# boatcc.net
KiCad netlist of a schematic drawn in EAGLE
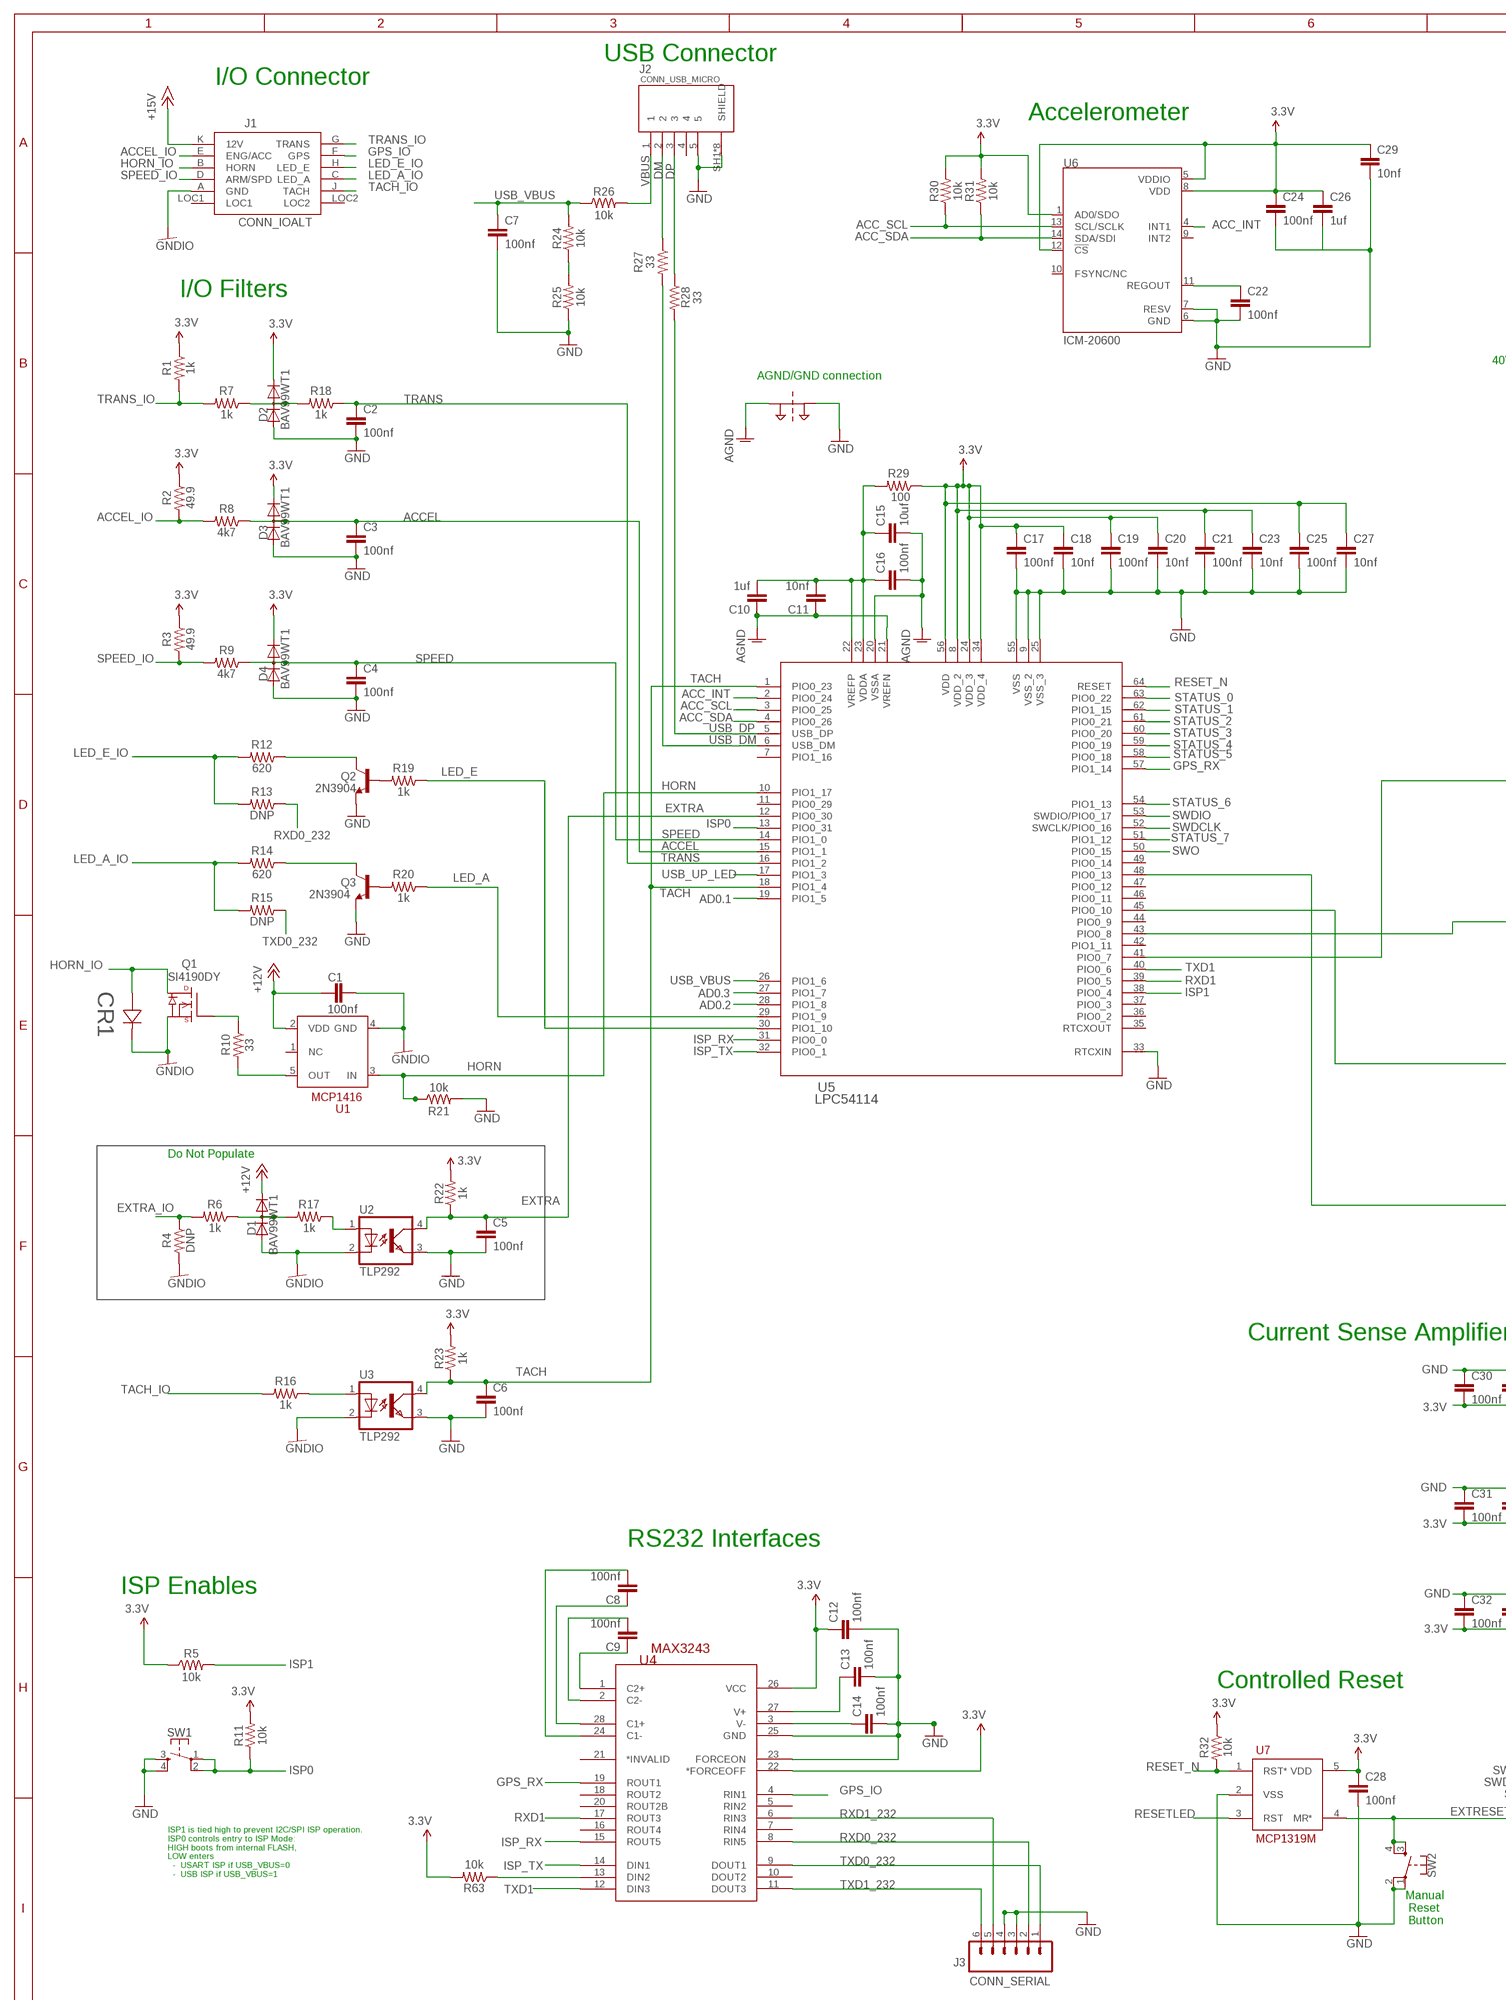
[diagram p0: schematic, sheet 1, part 1 of 2]
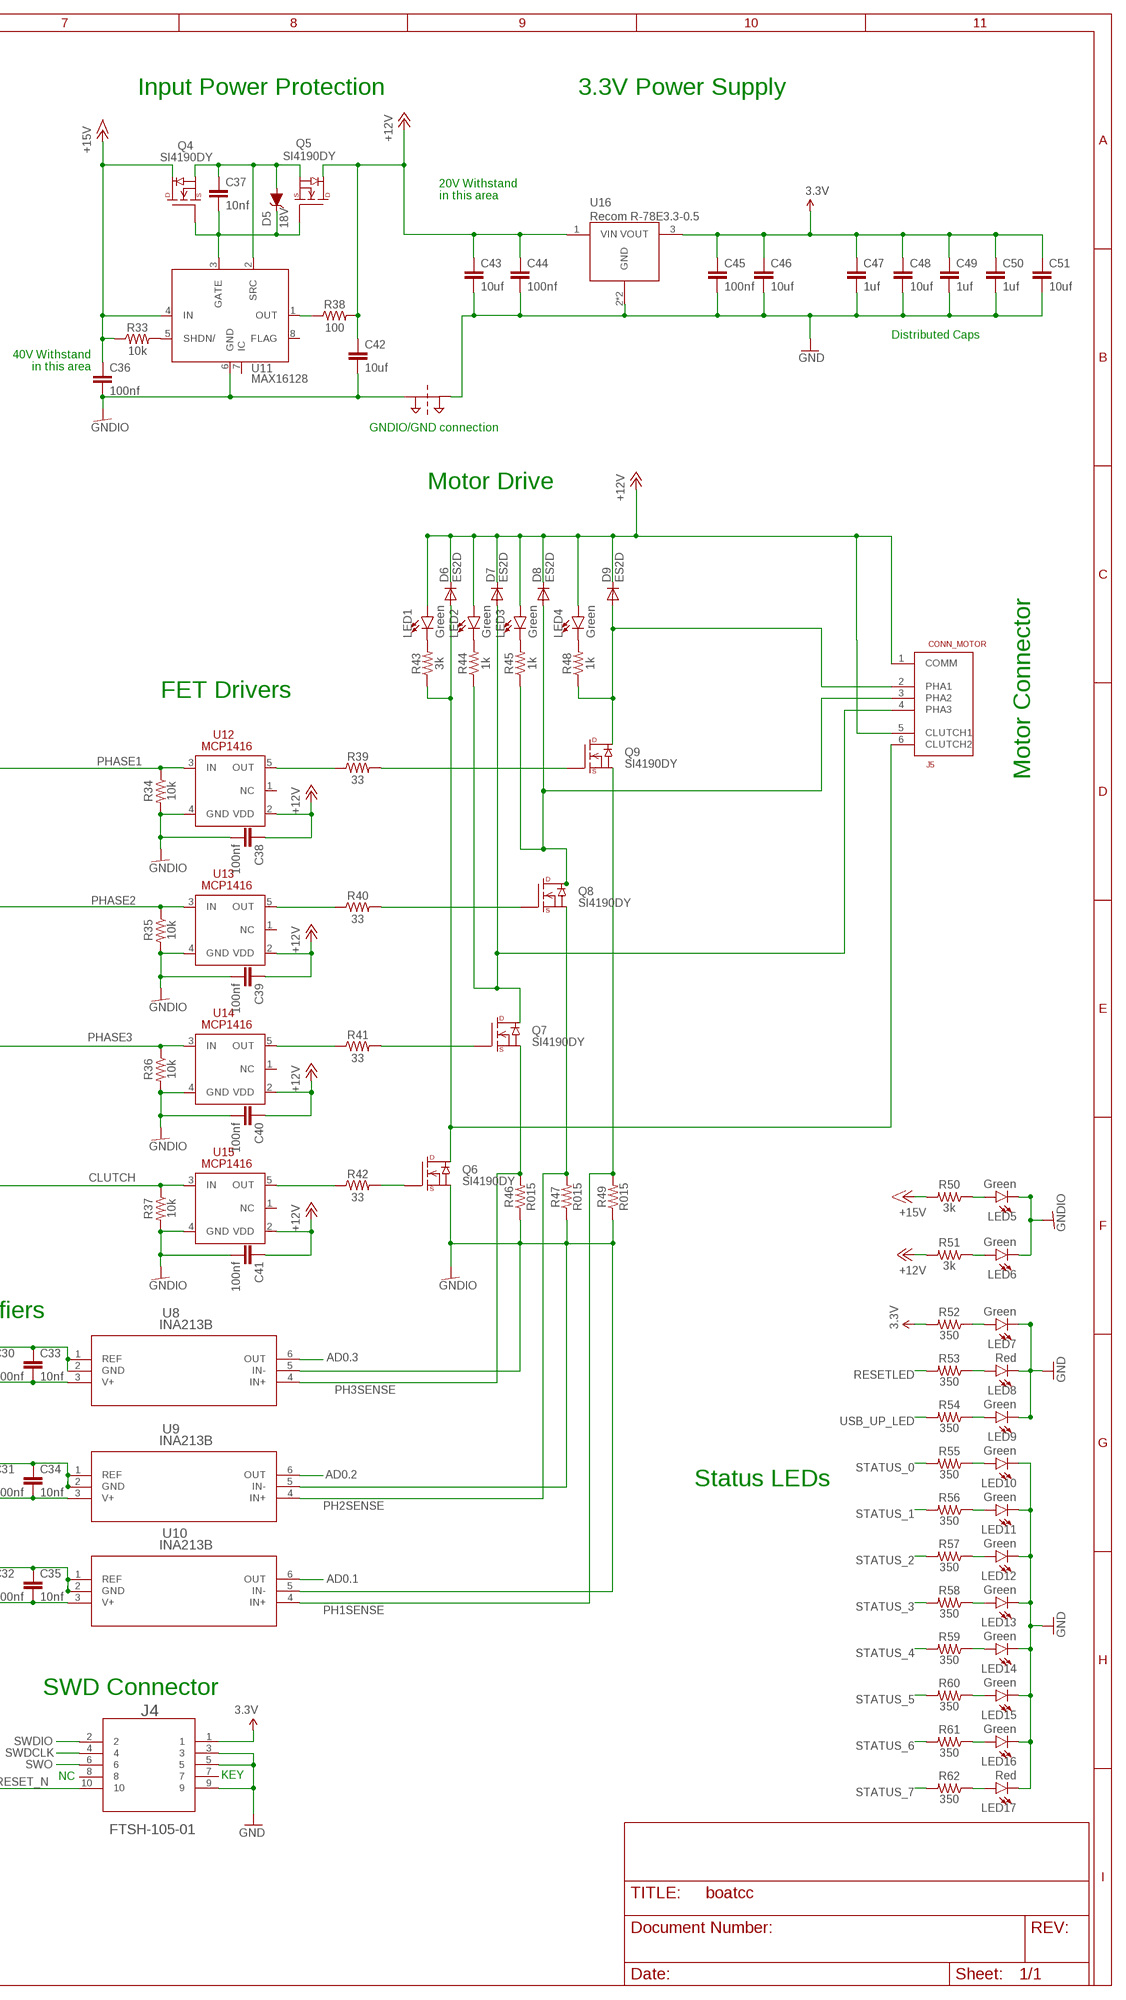
[diagram p1: schematic, sheet 1, part 2 of 2]

(export (version "E")
  (design (tool "Eeschema 10.0.6"))
  (components
    (comp (ref "C1")
      (value "100nf")
      (footprint "eagle-import:0805")
      (libsource (lib "eagle-import") (part "1CAP-0805"))
    )
    (comp (ref "C2")
      (value "100nf")
      (footprint "eagle-import:0805")
      (libsource (lib "eagle-import") (part "1CAP-0805"))
    )
    (comp (ref "C3")
      (value "100nf")
      (footprint "eagle-import:0805")
      (libsource (lib "eagle-import") (part "1CAP-0805"))
    )
    (comp (ref "C4")
      (value "100nf")
      (footprint "eagle-import:0805")
      (libsource (lib "eagle-import") (part "1CAP-0805"))
    )
    (comp (ref "C5")
      (value "100nf")
      (footprint "eagle-import:0805")
      (libsource (lib "eagle-import") (part "1CAP-0805"))
    )
    (comp (ref "C6")
      (value "100nf")
      (footprint "eagle-import:0805")
      (libsource (lib "eagle-import") (part "1CAP-0805"))
    )
    (comp (ref "C7")
      (value "100nf")
      (footprint "eagle-import:0805")
      (libsource (lib "eagle-import") (part "1CAP-0805"))
    )
    (comp (ref "C8")
      (value "100nf")
      (footprint "eagle-import:0805")
      (libsource (lib "eagle-import") (part "1CAP-0805"))
    )
    (comp (ref "C9")
      (value "100nf")
      (footprint "eagle-import:0805")
      (libsource (lib "eagle-import") (part "1CAP-0805"))
    )
    (comp (ref "C10")
      (value "1uf")
      (footprint "eagle-import:0805")
      (libsource (lib "eagle-import") (part "1CAP-0805"))
    )
    (comp (ref "C11")
      (value "10nf")
      (footprint "eagle-import:0805")
      (libsource (lib "eagle-import") (part "1CAP-0805"))
    )
    (comp (ref "C12")
      (value "100nf")
      (footprint "eagle-import:0805")
      (libsource (lib "eagle-import") (part "1CAP-0805"))
    )
    (comp (ref "C13")
      (value "100nf")
      (footprint "eagle-import:0805")
      (libsource (lib "eagle-import") (part "1CAP-0805"))
    )
    (comp (ref "C14")
      (value "100nf")
      (footprint "eagle-import:0805")
      (libsource (lib "eagle-import") (part "1CAP-0805"))
    )
    (comp (ref "C15")
      (value "10uf")
      (footprint "eagle-import:0805")
      (libsource (lib "eagle-import") (part "1CAP-0805"))
    )
    (comp (ref "C16")
      (value "100nf")
      (footprint "eagle-import:0805")
      (libsource (lib "eagle-import") (part "1CAP-0805"))
    )
    (comp (ref "C17")
      (value "100nf")
      (footprint "eagle-import:0805")
      (libsource (lib "eagle-import") (part "1CAP-0805"))
    )
    (comp (ref "C18")
      (value "10nf")
      (footprint "eagle-import:0805")
      (libsource (lib "eagle-import") (part "1CAP-0805"))
    )
    (comp (ref "C19")
      (value "100nf")
      (footprint "eagle-import:0805")
      (libsource (lib "eagle-import") (part "1CAP-0805"))
    )
    (comp (ref "C20")
      (value "10nf")
      (footprint "eagle-import:0805")
      (libsource (lib "eagle-import") (part "1CAP-0805"))
    )
    (comp (ref "C21")
      (value "100nf")
      (footprint "eagle-import:0805")
      (libsource (lib "eagle-import") (part "1CAP-0805"))
    )
    (comp (ref "C22")
      (value "100nf")
      (footprint "eagle-import:0805")
      (libsource (lib "eagle-import") (part "1CAP-0805"))
    )
    (comp (ref "C23")
      (value "10nf")
      (footprint "eagle-import:0805")
      (libsource (lib "eagle-import") (part "1CAP-0805"))
    )
    (comp (ref "C24")
      (value "100nf")
      (footprint "eagle-import:0805")
      (libsource (lib "eagle-import") (part "1CAP-0805"))
    )
    (comp (ref "C25")
      (value "100nf")
      (footprint "eagle-import:0805")
      (libsource (lib "eagle-import") (part "1CAP-0805"))
    )
    (comp (ref "C26")
      (value "1uf")
      (footprint "eagle-import:0805")
      (libsource (lib "eagle-import") (part "1CAP-0805"))
    )
    (comp (ref "C27")
      (value "10nf")
      (footprint "eagle-import:0805")
      (libsource (lib "eagle-import") (part "1CAP-0805"))
    )
    (comp (ref "C28")
      (value "100nf")
      (footprint "eagle-import:0805")
      (libsource (lib "eagle-import") (part "1CAP-0805"))
    )
    (comp (ref "C29")
      (value "10nf")
      (footprint "eagle-import:0805")
      (libsource (lib "eagle-import") (part "1CAP-0805"))
    )
    (comp (ref "C30")
      (value "100nf")
      (footprint "eagle-import:0805")
      (libsource (lib "eagle-import") (part "1CAP-0805"))
    )
    (comp (ref "C31")
      (value "100nf")
      (footprint "eagle-import:0805")
      (libsource (lib "eagle-import") (part "1CAP-0805"))
    )
    (comp (ref "C32")
      (value "100nf")
      (footprint "eagle-import:0805")
      (libsource (lib "eagle-import") (part "1CAP-0805"))
    )
    (comp (ref "C33")
      (value "10nf")
      (footprint "eagle-import:0805")
      (libsource (lib "eagle-import") (part "1CAP-0805"))
    )
    (comp (ref "C34")
      (value "10nf")
      (footprint "eagle-import:0805")
      (libsource (lib "eagle-import") (part "1CAP-0805"))
    )
    (comp (ref "C35")
      (value "10nf")
      (footprint "eagle-import:0805")
      (libsource (lib "eagle-import") (part "1CAP-0805"))
    )
    (comp (ref "C36")
      (value "100nf")
      (footprint "eagle-import:0805")
      (libsource (lib "eagle-import") (part "1CAP-0805"))
    )
    (comp (ref "C37")
      (value "10nf")
      (footprint "eagle-import:0805")
      (libsource (lib "eagle-import") (part "1CAP-0805"))
    )
    (comp (ref "C38")
      (value "100nf")
      (footprint "eagle-import:0805")
      (libsource (lib "eagle-import") (part "1CAP-0805"))
    )
    (comp (ref "C39")
      (value "100nf")
      (footprint "eagle-import:0805")
      (libsource (lib "eagle-import") (part "1CAP-0805"))
    )
    (comp (ref "C40")
      (value "100nf")
      (footprint "eagle-import:0805")
      (libsource (lib "eagle-import") (part "1CAP-0805"))
    )
    (comp (ref "C41")
      (value "100nf")
      (footprint "eagle-import:0805")
      (libsource (lib "eagle-import") (part "1CAP-0805"))
    )
    (comp (ref "C42")
      (value "10uf")
      (footprint "eagle-import:0805")
      (libsource (lib "eagle-import") (part "1CAP-0805"))
    )
    (comp (ref "C43")
      (value "10uf")
      (footprint "eagle-import:0805")
      (libsource (lib "eagle-import") (part "1CAP-0805"))
    )
    (comp (ref "C44")
      (value "100nf")
      (footprint "eagle-import:0805")
      (libsource (lib "eagle-import") (part "1CAP-0805"))
    )
    (comp (ref "C45")
      (value "100nf")
      (footprint "eagle-import:0805")
      (libsource (lib "eagle-import") (part "1CAP-0805"))
    )
    (comp (ref "C46")
      (value "10uf")
      (footprint "eagle-import:0805")
      (libsource (lib "eagle-import") (part "1CAP-0805"))
    )
    (comp (ref "C47")
      (value "1uf")
      (footprint "eagle-import:0805")
      (libsource (lib "eagle-import") (part "1CAP-0805"))
    )
    (comp (ref "C48")
      (value "10uf")
      (footprint "eagle-import:0805")
      (libsource (lib "eagle-import") (part "1CAP-0805"))
    )
    (comp (ref "C49")
      (value "1uf")
      (footprint "eagle-import:0805")
      (libsource (lib "eagle-import") (part "1CAP-0805"))
    )
    (comp (ref "C50")
      (value "1uf")
      (footprint "eagle-import:0805")
      (libsource (lib "eagle-import") (part "1CAP-0805"))
    )
    (comp (ref "C51")
      (value "10uf")
      (footprint "eagle-import:0805")
      (libsource (lib "eagle-import") (part "1CAP-0805"))
    )
    (comp (ref "CR1")
      (value "SMAJ45CASMASERIES-M")
      (footprint "eagle-import:SMASERIES-M")
      (fields
        (field (name "MANUFACTURER_PART_NUMBER") "SMAJ45CA")
        (field (name "DIGI-KEY_PART_NUMBER") "SMAJ24CALFCT-ND")
        (field (name "MANUFACTURER_PART_NUMBER_1") "SMAJ24CA")
      )
      (libsource (lib "eagle-import") (part "SMAJ45CASMASERIES-M"))
    )
    (comp (ref "D1")
      (value "BAV99WT1")
      (footprint "eagle-import:SC70")
      (fields
        (field (name "DIGI-KEY_PART_NUMBER") "BAV99WT1GOSCT-ND")
        (field (name "MF") "ON Semiconductor")
        (field (name "MP") "BAV99WT1G ")
      )
      (libsource (lib "eagle-import") (part "BAV99WT1"))
    )
    (comp (ref "D2")
      (value "BAV99WT1")
      (footprint "eagle-import:SC70")
      (fields
        (field (name "DIGI-KEY_PART_NUMBER") "BAV99WT1GOSCT-ND")
        (field (name "MF") "ON Semiconductor")
        (field (name "MP") "BAV99WT1G ")
      )
      (libsource (lib "eagle-import") (part "BAV99WT1"))
    )
    (comp (ref "D3")
      (value "BAV99WT1")
      (footprint "eagle-import:SC70")
      (fields
        (field (name "DIGI-KEY_PART_NUMBER") "BAV99WT1GOSCT-ND")
        (field (name "MF") "ON Semiconductor")
        (field (name "MP") "BAV99WT1G ")
      )
      (libsource (lib "eagle-import") (part "BAV99WT1"))
    )
    (comp (ref "D4")
      (value "BAV99WT1")
      (footprint "eagle-import:SC70")
      (fields
        (field (name "DIGI-KEY_PART_NUMBER") "BAV99WT1GOSCT-ND")
        (field (name "MF") "ON Semiconductor")
        (field (name "MP") "BAV99WT1G ")
      )
      (libsource (lib "eagle-import") (part "BAV99WT1"))
    )
    (comp (ref "D5")
      (value "18V")
      (footprint "eagle-import:SOD-323")
      (fields
        (field (name "DIGI-KEY_PART_NUMBER") "MM3Z18VT1GOSCT-ND ")
        (field (name "MF") "ON Semiconductor")
        (field (name "MP") "MM3Z18VT1G ")
      )
      (libsource (lib "eagle-import") (part "DIODE-ZENER-MM3Z3V3T1G"))
    )
    (comp (ref "D6")
      (value "ES2D")
      (footprint "eagle-import:SMB")
      (fields (field (name "DIGI-KEY_PART_NUMBER") "ES2DFSCT-ND") (field (name "MF") "ON Semiconductor"))
      (libsource (lib "eagle-import") (part "ES2D"))
    )
    (comp (ref "D7")
      (value "ES2D")
      (footprint "eagle-import:SMB")
      (fields (field (name "DIGI-KEY_PART_NUMBER") "ES2DFSCT-ND") (field (name "MF") "ON Semiconductor"))
      (libsource (lib "eagle-import") (part "ES2D"))
    )
    (comp (ref "D8")
      (value "ES2D")
      (footprint "eagle-import:SMB")
      (fields (field (name "DIGI-KEY_PART_NUMBER") "ES2DFSCT-ND") (field (name "MF") "ON Semiconductor"))
      (libsource (lib "eagle-import") (part "ES2D"))
    )
    (comp (ref "D9")
      (value "ES2D")
      (footprint "eagle-import:SMB")
      (fields (field (name "DIGI-KEY_PART_NUMBER") "ES2DFSCT-ND") (field (name "MF") "ON Semiconductor"))
      (libsource (lib "eagle-import") (part "ES2D"))
    )
    (comp (ref "J1")
      (value "CONN_IOALT")
      (footprint "eagle-import:CONN_IO")
      (libsource (lib "eagle-import") (part "CONN_IOALT"))
    )
    (comp (ref "J2")
      (value "CONN_USB_MICRO")
      (footprint "eagle-import:MOLEX_1050170001")
      (fields
        (field (name "DIGI-KEY_PART_NUMBER") "WM1399CT-ND")
        (field (name "MF") "Molex, LLC")
        (field (name "MP") "1050170001")
      )
      (libsource (lib "eagle-import") (part "USB_MICRO"))
    )
    (comp (ref "J3")
      (value "CONN_SERIAL")
      (footprint "eagle-import:1X06_LOCK")
      (libsource (lib "eagle-import") (part "CONN_06LOCK"))
    )
    (comp (ref "J4")
      (value "FTSH-105-01")
      (footprint "eagle-import:SAMTEC-FTSH-105-01-X-DV")
      (fields
        (field (name "DIGI-KEY_PART_NUMBER") "SAM13933CT-ND")
        (field (name "MF") "Samtec Inc.")
        (field (name "MP") "FTSH-105-01-L-DV-007-P-TR")
      )
      (libsource (lib "eagle-import") (part "SAMTEC-FTSH-105-01-X-DVJ"))
    )
    (comp (ref "J5")
      (value "CONN_MOTOR")
      (footprint "eagle-import:CONN_MOTOR")
      (libsource (lib "eagle-import") (part "CONN_MOTOR"))
    )
    (comp (ref "LED1")
      (value "Green")
      (footprint "eagle-import:LED_0805")
      (fields
        (field (name "DIGI-KEY_PART_NUMBER") "732-4986-1-ND ")
        (field (name "DIGI-KEY_PURCHASE_URL") "https://www.digikey.com/product-detail/en/wurth-electronics-inc/150080VS75000/732-4986-1-ND/4489922")
        (field (name "MF") "WURTH Electronics")
        (field (name "MP") "150080VS75000")
      )
      (libsource (lib "eagle-import") (part "1LED0805"))
    )
    (comp (ref "LED2")
      (value "Green")
      (footprint "eagle-import:LED_0805")
      (fields
        (field (name "DIGI-KEY_PART_NUMBER") "732-4986-1-ND ")
        (field (name "DIGI-KEY_PURCHASE_URL") "https://www.digikey.com/product-detail/en/wurth-electronics-inc/150080VS75000/732-4986-1-ND/4489922")
        (field (name "MF") "WURTH Electronics")
        (field (name "MP") "150080VS75000")
      )
      (libsource (lib "eagle-import") (part "1LED0805"))
    )
    (comp (ref "LED3")
      (value "Green")
      (footprint "eagle-import:LED_0805")
      (fields
        (field (name "DIGI-KEY_PART_NUMBER") "732-4986-1-ND ")
        (field (name "DIGI-KEY_PURCHASE_URL") "https://www.digikey.com/product-detail/en/wurth-electronics-inc/150080VS75000/732-4986-1-ND/4489922")
        (field (name "MF") "WURTH Electronics")
        (field (name "MP") "150080VS75000")
      )
      (libsource (lib "eagle-import") (part "1LED0805"))
    )
    (comp (ref "LED4")
      (value "Green")
      (footprint "eagle-import:LED_0805")
      (fields
        (field (name "DIGI-KEY_PART_NUMBER") "732-4986-1-ND ")
        (field (name "DIGI-KEY_PURCHASE_URL") "https://www.digikey.com/product-detail/en/wurth-electronics-inc/150080VS75000/732-4986-1-ND/4489922")
        (field (name "MF") "WURTH Electronics")
        (field (name "MP") "150080VS75000")
      )
      (libsource (lib "eagle-import") (part "1LED0805"))
    )
    (comp (ref "LED5")
      (value "Green")
      (footprint "eagle-import:LED_0805")
      (fields
        (field (name "DIGI-KEY_PART_NUMBER") "732-4986-1-ND ")
        (field (name "DIGI-KEY_PURCHASE_URL") "https://www.digikey.com/product-detail/en/wurth-electronics-inc/150080VS75000/732-4986-1-ND/4489922")
        (field (name "MF") "WURTH Electronics")
        (field (name "MP") "150080VS75000")
      )
      (libsource (lib "eagle-import") (part "1LED0805"))
    )
    (comp (ref "LED6")
      (value "Green")
      (footprint "eagle-import:LED_0805")
      (fields
        (field (name "DIGI-KEY_PART_NUMBER") "732-4986-1-ND ")
        (field (name "DIGI-KEY_PURCHASE_URL") "https://www.digikey.com/product-detail/en/wurth-electronics-inc/150080VS75000/732-4986-1-ND/4489922")
        (field (name "MF") "WURTH Electronics")
        (field (name "MP") "150080VS75000")
      )
      (libsource (lib "eagle-import") (part "1LED0805"))
    )
    (comp (ref "LED7")
      (value "Green")
      (footprint "eagle-import:LED_0805")
      (fields
        (field (name "DIGI-KEY_PART_NUMBER") "732-4986-1-ND ")
        (field (name "DIGI-KEY_PURCHASE_URL") "https://www.digikey.com/product-detail/en/wurth-electronics-inc/150080VS75000/732-4986-1-ND/4489922")
        (field (name "MF") "WURTH Electronics")
        (field (name "MP") "150080VS75000")
      )
      (libsource (lib "eagle-import") (part "1LED0805"))
    )
    (comp (ref "LED8")
      (value "Red")
      (footprint "eagle-import:LED_0805")
      (fields
        (field (name "DIGI-KEY_PART_NUMBER") "732-4984-1-ND ")
        (field (name "DIGI-KEY_PURCHASE_URL") "https://www.digikey.com/product-detail/en/wurth-electronics-inc/150080RS75000/732-4984-1-ND/4489916")
        (field (name "MF") "WURTH Electronics")
        (field (name "MP") "150080RS75000 ")
      )
      (libsource (lib "eagle-import") (part "1LED0805"))
    )
    (comp (ref "LED9")
      (value "Green")
      (footprint "eagle-import:LED_0805")
      (fields
        (field (name "DIGI-KEY_PART_NUMBER") "732-4986-1-ND ")
        (field (name "MF") "WURTH Electronics")
        (field (name "MP") "150080VS75000")
      )
      (libsource (lib "eagle-import") (part "1LED0805"))
    )
    (comp (ref "LED10")
      (value "Green")
      (footprint "eagle-import:LED_0805")
      (fields
        (field (name "DIGI-KEY_PART_NUMBER") "732-4986-1-ND ")
        (field (name "DIGI-KEY_PURCHASE_URL") "https://www.digikey.com/product-detail/en/wurth-electronics-inc/150080VS75000/732-4986-1-ND/4489922")
        (field (name "MF") "WURTH Electronics")
        (field (name "MP") "150080VS75000")
      )
      (libsource (lib "eagle-import") (part "1LED0805"))
    )
    (comp (ref "LED11")
      (value "Green")
      (footprint "eagle-import:LED_0805")
      (fields
        (field (name "DIGI-KEY_PART_NUMBER") "732-4986-1-ND ")
        (field (name "DIGI-KEY_PURCHASE_URL") "https://www.digikey.com/product-detail/en/wurth-electronics-inc/150080VS75000/732-4986-1-ND/4489922")
        (field (name "MF") "WURTH Electronics")
        (field (name "MP") "150080VS75000")
      )
      (libsource (lib "eagle-import") (part "1LED0805"))
    )
    (comp (ref "LED12")
      (value "Green")
      (footprint "eagle-import:LED_0805")
      (fields
        (field (name "DIGI-KEY_PART_NUMBER") "732-4986-1-ND ")
        (field (name "DIGI-KEY_PURCHASE_URL") "https://www.digikey.com/product-detail/en/wurth-electronics-inc/150080VS75000/732-4986-1-ND/4489922")
        (field (name "MF") "WURTH Electronics")
        (field (name "MP") "150080VS75000")
      )
      (libsource (lib "eagle-import") (part "1LED0805"))
    )
    (comp (ref "LED13")
      (value "Green")
      (footprint "eagle-import:LED_0805")
      (fields
        (field (name "DIGI-KEY_PART_NUMBER") "732-4986-1-ND ")
        (field (name "DIGI-KEY_PURCHASE_URL") "https://www.digikey.com/product-detail/en/wurth-electronics-inc/150080VS75000/732-4986-1-ND/4489922")
        (field (name "MF") "WURTH Electronics")
        (field (name "MP") "150080VS75000")
      )
      (libsource (lib "eagle-import") (part "1LED0805"))
    )
    (comp (ref "LED14")
      (value "Green")
      (footprint "eagle-import:LED_0805")
      (fields
        (field (name "DIGI-KEY_PART_NUMBER") "732-4986-1-ND ")
        (field (name "DIGI-KEY_PURCHASE_URL") "https://www.digikey.com/product-detail/en/wurth-electronics-inc/150080VS75000/732-4986-1-ND/4489922")
        (field (name "MF") "WURTH Electronics")
        (field (name "MP") "150080VS75000")
      )
      (libsource (lib "eagle-import") (part "1LED0805"))
    )
    (comp (ref "LED15")
      (value "Green")
      (footprint "eagle-import:LED_0805")
      (fields
        (field (name "DIGI-KEY_PART_NUMBER") "732-4986-1-ND ")
        (field (name "DIGI-KEY_PURCHASE_URL") "https://www.digikey.com/product-detail/en/wurth-electronics-inc/150080VS75000/732-4986-1-ND/4489922")
        (field (name "MF") "WURTH Electronics")
        (field (name "MP") "150080VS75000")
      )
      (libsource (lib "eagle-import") (part "1LED0805"))
    )
    (comp (ref "LED16")
      (value "Green")
      (footprint "eagle-import:LED_0805")
      (fields
        (field (name "DIGI-KEY_PART_NUMBER") "732-4986-1-ND ")
        (field (name "DIGI-KEY_PURCHASE_URL") "https://www.digikey.com/product-detail/en/wurth-electronics-inc/150080VS75000/732-4986-1-ND/4489922")
        (field (name "MF") "WURTH Electronics")
        (field (name "MP") "150080VS75000")
      )
      (libsource (lib "eagle-import") (part "1LED0805"))
    )
    (comp (ref "LED17")
      (value "Red")
      (footprint "eagle-import:LED_0805")
      (fields
        (field (name "DIGI-KEY_PART_NUMBER") "732-4984-1-ND ")
        (field (name "DIGI-KEY_PURCHASE_URL") "https://www.digikey.com/product-detail/en/wurth-electronics-inc/150080RS75000/732-4984-1-ND/4489916")
        (field (name "MF") "WURTH Electronics")
        (field (name "MP") "150080RS75000 ")
      )
      (libsource (lib "eagle-import") (part "1LED0805"))
    )
    (comp (ref "Q1")
      (value "SI4190DY")
      (footprint "eagle-import:SO-8")
      (fields (field (name "DIGI-KEY_PART_NUMBER") "SI4190ADY-T1-GE3") (field (name "MF") "Vishay Siliconix"))
      (libsource (lib "eagle-import") (part "SI4190DY"))
    )
    (comp (ref "Q2")
      (value "2N3904")
      (footprint "eagle-import:SOT23-3")
      (fields
        (field (name "DIGI-KEY_PART_NUMBER") "MMBT2222AWT1GOSCT-ND")
        (field (name "MF") "ON Semiconductor")
        (field (name "MP") "MMBT2222AWT1G")
      )
      (libsource (lib "eagle-import") (part "TRANS_NPN-MMBT2222AL"))
    )
    (comp (ref "Q3")
      (value "2N3904")
      (footprint "eagle-import:SOT23-3")
      (fields
        (field (name "DIGI-KEY_PART_NUMBER") "MMBT2222AWT1GOSCT-ND")
        (field (name "MF") "ON Semiconductor")
        (field (name "MP") "MMBT2222AWT1G")
      )
      (libsource (lib "eagle-import") (part "TRANS_NPN-MMBT2222AL"))
    )
    (comp (ref "Q4")
      (value "SI4190DY")
      (footprint "eagle-import:SO-8")
      (fields (field (name "DIGI-KEY_PART_NUMBER") "SI4190ADY-T1-GE3") (field (name "MF") "Vishay Siliconix"))
      (libsource (lib "eagle-import") (part "SI4190DY"))
    )
    (comp (ref "Q5")
      (value "SI4190DY")
      (footprint "eagle-import:SO-8")
      (fields (field (name "DIGI-KEY_PART_NUMBER") "SI4190ADY-T1-GE3") (field (name "MF") "Vishay Siliconix"))
      (libsource (lib "eagle-import") (part "SI4190DY"))
    )
    (comp (ref "Q6")
      (value "SI4190DY")
      (footprint "eagle-import:SO-8")
      (fields (field (name "DIGI-KEY_PART_NUMBER") "SI4190ADY-T1-GE3") (field (name "MF") "Vishay Siliconix"))
      (libsource (lib "eagle-import") (part "SI4190DY"))
    )
    (comp (ref "Q7")
      (value "SI4190DY")
      (footprint "eagle-import:SO-8")
      (fields (field (name "DIGI-KEY_PART_NUMBER") "SI4190ADY-T1-GE3") (field (name "MF") "Vishay Siliconix"))
      (libsource (lib "eagle-import") (part "SI4190DY"))
    )
    (comp (ref "Q8")
      (value "SI4190DY")
      (footprint "eagle-import:SO-8")
      (fields (field (name "DIGI-KEY_PART_NUMBER") "SI4190ADY-T1-GE3") (field (name "MF") "Vishay Siliconix"))
      (libsource (lib "eagle-import") (part "SI4190DY"))
    )
    (comp (ref "Q9")
      (value "SI4190DY")
      (footprint "eagle-import:SO-8")
      (fields (field (name "DIGI-KEY_PART_NUMBER") "SI4190ADY-T1-GE3") (field (name "MF") "Vishay Siliconix"))
      (libsource (lib "eagle-import") (part "SI4190DY"))
    )
    (comp (ref "R1")
      (value "1k")
      (footprint "eagle-import:0805")
      (libsource (lib "eagle-import") (part "1RES-0805"))
    )
    (comp (ref "R2")
      (value "49.9")
      (footprint "eagle-import:0805")
      (libsource (lib "eagle-import") (part "1RES-0805"))
    )
    (comp (ref "R3")
      (value "49.9")
      (footprint "eagle-import:0805")
      (libsource (lib "eagle-import") (part "1RES-0805"))
    )
    (comp (ref "R4")
      (value "DNP")
      (footprint "eagle-import:0805")
      (libsource (lib "eagle-import") (part "1RES-0805"))
    )
    (comp (ref "R5")
      (value "10k")
      (footprint "eagle-import:0805")
      (libsource (lib "eagle-import") (part "1RES-0805"))
    )
    (comp (ref "R6")
      (value "1k")
      (footprint "eagle-import:0805")
      (libsource (lib "eagle-import") (part "1RES-0805"))
    )
    (comp (ref "R7")
      (value "1k")
      (footprint "eagle-import:0805")
      (libsource (lib "eagle-import") (part "1RES-0805"))
    )
    (comp (ref "R8")
      (value "4k7")
      (footprint "eagle-import:0805")
      (libsource (lib "eagle-import") (part "1RES-0805"))
    )
    (comp (ref "R9")
      (value "4k7")
      (footprint "eagle-import:0805")
      (libsource (lib "eagle-import") (part "1RES-0805"))
    )
    (comp (ref "R10")
      (value "33")
      (footprint "eagle-import:0805")
      (libsource (lib "eagle-import") (part "1RES-0805"))
    )
    (comp (ref "R11")
      (value "10k")
      (footprint "eagle-import:0805")
      (libsource (lib "eagle-import") (part "1RES-0805"))
    )
    (comp (ref "R12")
      (value "620")
      (footprint "eagle-import:0805")
      (libsource (lib "eagle-import") (part "1RES-0805"))
    )
    (comp (ref "R13")
      (value "DNP")
      (footprint "eagle-import:0805")
      (libsource (lib "eagle-import") (part "1RES-0805"))
    )
    (comp (ref "R14")
      (value "620")
      (footprint "eagle-import:0805")
      (libsource (lib "eagle-import") (part "1RES-0805"))
    )
    (comp (ref "R15")
      (value "DNP")
      (footprint "eagle-import:0805")
      (libsource (lib "eagle-import") (part "1RES-0805"))
    )
    (comp (ref "R16")
      (value "1k")
      (footprint "eagle-import:0805")
      (libsource (lib "eagle-import") (part "1RES-0805"))
    )
    (comp (ref "R17")
      (value "1k")
      (footprint "eagle-import:0805")
      (libsource (lib "eagle-import") (part "1RES-0805"))
    )
    (comp (ref "R18")
      (value "1k")
      (footprint "eagle-import:0805")
      (libsource (lib "eagle-import") (part "1RES-0805"))
    )
    (comp (ref "R19")
      (value "1k")
      (footprint "eagle-import:0805")
      (libsource (lib "eagle-import") (part "1RES-0805"))
    )
    (comp (ref "R20")
      (value "1k")
      (footprint "eagle-import:0805")
      (libsource (lib "eagle-import") (part "1RES-0805"))
    )
    (comp (ref "R21")
      (value "10k")
      (footprint "eagle-import:0805")
      (libsource (lib "eagle-import") (part "1RES-0805"))
    )
    (comp (ref "R22")
      (value "1k")
      (footprint "eagle-import:0805")
      (libsource (lib "eagle-import") (part "1RES-0805"))
    )
    (comp (ref "R23")
      (value "1k")
      (footprint "eagle-import:0805")
      (libsource (lib "eagle-import") (part "1RES-0805"))
    )
    (comp (ref "R24")
      (value "10k")
      (footprint "eagle-import:0805")
      (libsource (lib "eagle-import") (part "1RES-0805"))
    )
    (comp (ref "R25")
      (value "10k")
      (footprint "eagle-import:0805")
      (libsource (lib "eagle-import") (part "1RES-0805"))
    )
    (comp (ref "R26")
      (value "10k")
      (footprint "eagle-import:0805")
      (libsource (lib "eagle-import") (part "1RES-0805"))
    )
    (comp (ref "R27")
      (value "33")
      (footprint "eagle-import:0805")
      (libsource (lib "eagle-import") (part "1RES-0805"))
    )
    (comp (ref "R28")
      (value "33")
      (footprint "eagle-import:0805")
      (libsource (lib "eagle-import") (part "1RES-0805"))
    )
    (comp (ref "R29")
      (value "100")
      (footprint "eagle-import:0805")
      (libsource (lib "eagle-import") (part "1RES-0805"))
    )
    (comp (ref "R30")
      (value "10k")
      (footprint "eagle-import:0805")
      (libsource (lib "eagle-import") (part "1RES-0805"))
    )
    (comp (ref "R31")
      (value "10k")
      (footprint "eagle-import:0805")
      (libsource (lib "eagle-import") (part "1RES-0805"))
    )
    (comp (ref "R32")
      (value "10k")
      (footprint "eagle-import:0805")
      (libsource (lib "eagle-import") (part "1RES-0805"))
    )
    (comp (ref "R33")
      (value "10k")
      (footprint "eagle-import:0805")
      (libsource (lib "eagle-import") (part "1RES-0805"))
    )
    (comp (ref "R34")
      (value "10k")
      (footprint "eagle-import:0805")
      (libsource (lib "eagle-import") (part "1RES-0805"))
    )
    (comp (ref "R35")
      (value "10k")
      (footprint "eagle-import:0805")
      (libsource (lib "eagle-import") (part "1RES-0805"))
    )
    (comp (ref "R36")
      (value "10k")
      (footprint "eagle-import:0805")
      (libsource (lib "eagle-import") (part "1RES-0805"))
    )
    (comp (ref "R37")
      (value "10k")
      (footprint "eagle-import:0805")
      (libsource (lib "eagle-import") (part "1RES-0805"))
    )
    (comp (ref "R38")
      (value "100")
      (footprint "eagle-import:0805")
      (libsource (lib "eagle-import") (part "1RES-0805"))
    )
    (comp (ref "R39")
      (value "33")
      (footprint "eagle-import:0805")
      (libsource (lib "eagle-import") (part "1RES-0805"))
    )
    (comp (ref "R40")
      (value "33")
      (footprint "eagle-import:0805")
      (libsource (lib "eagle-import") (part "1RES-0805"))
    )
    (comp (ref "R41")
      (value "33")
      (footprint "eagle-import:0805")
      (libsource (lib "eagle-import") (part "1RES-0805"))
    )
    (comp (ref "R42")
      (value "33")
      (footprint "eagle-import:0805")
      (libsource (lib "eagle-import") (part "1RES-0805"))
    )
    (comp (ref "R43")
      (value "3k")
      (footprint "eagle-import:0805")
      (libsource (lib "eagle-import") (part "1RES-0805"))
    )
    (comp (ref "R44")
      (value "1k")
      (footprint "eagle-import:0805")
      (libsource (lib "eagle-import") (part "1RES-0805"))
    )
    (comp (ref "R45")
      (value "1k")
      (footprint "eagle-import:0805")
      (libsource (lib "eagle-import") (part "1RES-0805"))
    )
    (comp (ref "R46")
      (value "R015")
      (footprint "eagle-import:1206")
      (fields (field (name "DIGI-KEY_PART_NUMBER") "408-1572-1-ND"))
      (libsource (lib "eagle-import") (part "1RES-1206"))
    )
    (comp (ref "R47")
      (value "R015")
      (footprint "eagle-import:1206")
      (fields (field (name "DIGI-KEY_PART_NUMBER") "408-1572-1-ND"))
      (libsource (lib "eagle-import") (part "1RES-1206"))
    )
    (comp (ref "R48")
      (value "1k")
      (footprint "eagle-import:0805")
      (libsource (lib "eagle-import") (part "1RES-0805"))
    )
    (comp (ref "R49")
      (value "R015")
      (footprint "eagle-import:1206")
      (fields (field (name "DIGI-KEY_PART_NUMBER") "408-1572-1-ND"))
      (libsource (lib "eagle-import") (part "1RES-1206"))
    )
    (comp (ref "R50")
      (value "3k")
      (footprint "eagle-import:0805")
      (libsource (lib "eagle-import") (part "1RES-0805"))
    )
    (comp (ref "R51")
      (value "3k")
      (footprint "eagle-import:0805")
      (libsource (lib "eagle-import") (part "1RES-0805"))
    )
    (comp (ref "R52")
      (value "350")
      (footprint "eagle-import:0805")
      (libsource (lib "eagle-import") (part "1RES-0805"))
    )
    (comp (ref "R53")
      (value "350")
      (footprint "eagle-import:0805")
      (libsource (lib "eagle-import") (part "1RES-0805"))
    )
    (comp (ref "R54")
      (value "350")
      (footprint "eagle-import:0805")
      (libsource (lib "eagle-import") (part "1RES-0805"))
    )
    (comp (ref "R55")
      (value "350")
      (footprint "eagle-import:0805")
      (libsource (lib "eagle-import") (part "1RES-0805"))
    )
    (comp (ref "R56")
      (value "350")
      (footprint "eagle-import:0805")
      (libsource (lib "eagle-import") (part "1RES-0805"))
    )
    (comp (ref "R57")
      (value "350")
      (footprint "eagle-import:0805")
      (libsource (lib "eagle-import") (part "1RES-0805"))
    )
    (comp (ref "R58")
      (value "350")
      (footprint "eagle-import:0805")
      (libsource (lib "eagle-import") (part "1RES-0805"))
    )
    (comp (ref "R59")
      (value "350")
      (footprint "eagle-import:0805")
      (libsource (lib "eagle-import") (part "1RES-0805"))
    )
    (comp (ref "R60")
      (value "350")
      (footprint "eagle-import:0805")
      (libsource (lib "eagle-import") (part "1RES-0805"))
    )
    (comp (ref "R61")
      (value "350")
      (footprint "eagle-import:0805")
      (libsource (lib "eagle-import") (part "1RES-0805"))
    )
    (comp (ref "R62")
      (value "350")
      (footprint "eagle-import:0805")
      (libsource (lib "eagle-import") (part "1RES-0805"))
    )
    (comp (ref "R63")
      (value "10k")
      (footprint "eagle-import:0805")
      (libsource (lib "eagle-import") (part "1RES-0805"))
    )
    (comp (ref "SUPPLY1")
      (value "2PT_GND_TIE")
      (footprint "eagle-import:2PT_GND_TIE")
      (libsource (lib "eagle-import") (part "2PT_GND_TIE"))
    )
    (comp (ref "SUPPLY2")
      (value "2PT_GND_TIE")
      (footprint "eagle-import:2PT_GND_TIE")
      (libsource (lib "eagle-import") (part "2PT_GND_TIE"))
    )
    (comp (ref "SW1")
      (value "MOMENTARY-SWITCH-SPST-2-SMD-5.2MM")
      (footprint "eagle-import:TACTILE_SWITCH_SMD_5.2MM")
      (fields
        (field (name "DIGI-KEY_PART_NUMBER") "CKN9104CT-ND")
        (field (name "MF") "C&K")
        (field (name "MP") "PTS525SM15SMTR2 LFS")
      )
      (libsource (lib "eagle-import") (part "MOMENTARY-SWITCH-SPST-2-SMD-5.2MM"))
    )
    (comp (ref "SW2")
      (value "MOMENTARY-SWITCH-SPST-2-SMD-5.2MM")
      (footprint "eagle-import:TACTILE_SWITCH_SMD_5.2MM")
      (fields
        (field (name "DIGI-KEY_PART_NUMBER") "CKN9104CT-ND")
        (field (name "MF") "C&K")
        (field (name "MP") "PTS525SM15SMTR2 LFS")
      )
      (libsource (lib "eagle-import") (part "MOMENTARY-SWITCH-SPST-2-SMD-5.2MM"))
    )
    (comp (ref "U1")
      (value "MCP1416")
      (footprint "eagle-import:SOT-23-5_MC-M")
      (fields
        (field (name "DIGI-KEY_PART_NUMBER") "MCP1416T-E/OTCT-ND")
        (field (name "MF") "Microchip Technology")
      )
      (libsource (lib "eagle-import") (part "MCP1416SOT-23-5_MCM"))
    )
    (comp (ref "U2")
      (value "TLP292")
      (footprint "eagle-import:MINI-FLAT-4")
      (fields
        (field (name "DIGI-KEY_PART_NUMBER") "TLP291(GB-TPSECT-ND ")
        (field (name "MF") "Toshiba Semiconductor")
        (field (name "MP") "TLP291(GB-TP,SE")
        (field (name "DIGI-KEY_PART_NUMBER_1") "TLP292(GB-TPLECT-ND ")
        (field (name "DIGI-KEY_PURCHASE_URL") "https://www.digikey.com/product-detail/en/toshiba-semiconductor-and-storage/TLP292-GB-TPLE/TLP292-GB-TPLECT-ND/4562959")
        (field (name "MP_1") "TLP292(GB-TPL,E")
      )
      (libsource (lib "eagle-import") (part "TLP290"))
    )
    (comp (ref "U3")
      (value "TLP292")
      (footprint "eagle-import:MINI-FLAT-4")
      (fields
        (field (name "DIGI-KEY_PART_NUMBER") "TLP291(GB-TPSECT-ND ")
        (field (name "MF") "Toshiba Semiconductor")
        (field (name "MP") "TLP291(GB-TP,SE")
        (field (name "DIGI-KEY_PART_NUMBER_1") "TLP292(GB-TPLECT-ND ")
        (field (name "DIGI-KEY_PURCHASE_URL") "https://www.digikey.com/product-detail/en/toshiba-semiconductor-and-storage/TLP292-GB-TPLE/TLP292-GB-TPLECT-ND/4562959")
        (field (name "MP_1") "TLP292(GB-TPL,E")
      )
      (libsource (lib "eagle-import") (part "TLP290"))
    )
    (comp (ref "U4")
      (value "MAX3243")
      (footprint "eagle-import:PW28-M")
      (fields
        (field (name "DIGI-KEY_PART_NUMBER") "296-19809-1-ND")
        (field (name "MF") "Texas Instruments")
        (field (name "MP") "MAX3243EIDWR")
      )
      (libsource (lib "eagle-import") (part "MAX3243_PW_28HEAVY"))
    )
    (comp (ref "U5")
      (value "LPC54114")
      (footprint "eagle-import:LQFP64_10X10-M")
      (fields
        (field (name "DIGI-KEY_PART_NUMBER") "568-13034-ND")
        (field (name "MF") "NXP")
        (field (name "MP") "LPC54114J256BD64QL")
      )
      (libsource (lib "eagle-import") (part "LPC5411XJXXXBD64LQFP64_10X10-M"))
    )
    (comp (ref "U6")
      (value "ICM-20600")
      (footprint "eagle-import:PQFN50P250X300X97-14N")
      (fields (field (name "DIGI-KEY_PART_NUMBER") "1428-1147-1-ND") (field (name "MF") "TDK InvenSense"))
      (libsource (lib "eagle-import") (part "ICM-20600"))
    )
    (comp (ref "U7")
      (value "MCP1319M")
      (footprint "eagle-import:SOT23-5")
      (fields
        (field (name "DIGI-KEY_PART_NUMBER") "MCP1319MT-29LE/OTCT-ND ")
        (field (name "MF") "Microchip Technology")
        (field (name "MP") "MCP1319MT-29LE/OT ")
      )
      (libsource (lib "eagle-import") (part "MCP1319M"))
    )
    (comp (ref "U8")
      (value "INA213B")
      (footprint "eagle-import:DCK6-M")
      (fields
        (field (name "MANUFACTURER_PART_NUMBER") "INA213AIDCKR")
        (field (name "DIGI-KEY_PART_NUMBER") "296-40129-1-ND")
        (field (name "MANUFACTURER_PART_NUMBER_1") "INA213BIDCKR")
      )
      (libsource (lib "eagle-import") (part "INA213AIDCKRDCK6-M"))
    )
    (comp (ref "U9")
      (value "INA213B")
      (footprint "eagle-import:DCK6-M")
      (fields
        (field (name "MANUFACTURER_PART_NUMBER") "INA213AIDCKR")
        (field (name "DIGI-KEY_PART_NUMBER") "296-40129-1-ND")
        (field (name "MANUFACTURER_PART_NUMBER_1") "INA213BIDCKR")
      )
      (libsource (lib "eagle-import") (part "INA213AIDCKRDCK6-M"))
    )
    (comp (ref "U10")
      (value "INA213B")
      (footprint "eagle-import:DCK6-M")
      (fields
        (field (name "MANUFACTURER_PART_NUMBER") "INA213AIDCKR")
        (field (name "DIGI-KEY_PART_NUMBER") "296-40129-1-ND")
        (field (name "MANUFACTURER_PART_NUMBER_1") "INA213BIDCKR")
      )
      (libsource (lib "eagle-import") (part "INA213AIDCKRDCK6-M"))
    )
    (comp (ref "U11")
      (value "MAX16128")
      (footprint "eagle-import:UMAX8")
      (fields
        (field (name "DIGI-KEY_PART_NUMBER") "MAX16129UADFD+-ND")
        (field (name "MF") "MAXIM")
        (field (name "MP") "MAX16129UADFD+")
      )
      (libsource (lib "eagle-import") (part "MAX16128"))
    )
    (comp (ref "U12")
      (value "MCP1416")
      (footprint "eagle-import:SOT-23-5_MC-M")
      (fields
        (field (name "DIGI-KEY_PART_NUMBER") "MCP1416T-E/OTCT-ND")
        (field (name "MF") "Microchip Technology")
      )
      (libsource (lib "eagle-import") (part "MCP1416SOT-23-5_MCM"))
    )
    (comp (ref "U13")
      (value "MCP1416")
      (footprint "eagle-import:SOT-23-5_MC-M")
      (fields
        (field (name "DIGI-KEY_PART_NUMBER") "MCP1416T-E/OTCT-ND")
        (field (name "MF") "Microchip Technology")
      )
      (libsource (lib "eagle-import") (part "MCP1416SOT-23-5_MCM"))
    )
    (comp (ref "U14")
      (value "MCP1416")
      (footprint "eagle-import:SOT-23-5_MC-M")
      (fields
        (field (name "DIGI-KEY_PART_NUMBER") "MCP1416T-E/OTCT-ND")
        (field (name "MF") "Microchip Technology")
      )
      (libsource (lib "eagle-import") (part "MCP1416SOT-23-5_MCM"))
    )
    (comp (ref "U15")
      (value "MCP1416")
      (footprint "eagle-import:SOT-23-5_MC-M")
      (fields
        (field (name "DIGI-KEY_PART_NUMBER") "MCP1416T-E/OTCT-ND")
        (field (name "MF") "Microchip Technology")
      )
      (libsource (lib "eagle-import") (part "MCP1416SOT-23-5_MCM"))
    )
    (comp (ref "U16")
      (value "Recom R-78E3.3-0.5")
      (footprint "eagle-import:D2PACK_A")
      (fields
        (field (name "ALT_DIGI-KEY_PART_NUMBER") "945-1661-5-ND")
        (field (name "DIGI-KEY_PART_NUMBER") "497-5225-1-ND ")
        (field (name "MF") "STMicroelectronics")
      )
      (libsource (lib "eagle-import") (part "LM2931_FIXEDD2PAK/TO263"))
    )
  )
  (nets
    (net (code "1") (name "+12V") (class "Default")
      (node (ref "C1") (pin "1") (pinfunction "1_1") (pintype "passive"))
      (node (ref "C38") (pin "1") (pinfunction "1_1") (pintype "passive"))
      (node (ref "C39") (pin "1") (pinfunction "1_1") (pintype "passive"))
      (node (ref "C40") (pin "1") (pinfunction "1_1") (pintype "passive"))
      (node (ref "C41") (pin "1") (pinfunction "1_1") (pintype "passive"))
      (node (ref "C42") (pin "1") (pinfunction "1_1") (pintype "passive"))
      (node (ref "C43") (pin "1") (pinfunction "1_1") (pintype "passive"))
      (node (ref "C44") (pin "1") (pinfunction "1_1") (pintype "passive"))
      (node (ref "D1") (pin "2") (pinfunction "C_2") (pintype "passive"))
      (node (ref "D6") (pin "C") (pinfunction "C_C") (pintype "passive"))
      (node (ref "D7") (pin "C") (pinfunction "C_C") (pintype "passive"))
      (node (ref "D8") (pin "C") (pinfunction "C_C") (pintype "passive"))
      (node (ref "D9") (pin "C") (pinfunction "C_C") (pintype "passive"))
      (node (ref "J5") (pin "1") (pinfunction "COMM_1") (pintype "bidirectional"))
      (node (ref "J5") (pin "5") (pinfunction "CLUTCH1_5") (pintype "bidirectional"))
      (node (ref "LED1") (pin "A") (pinfunction "A_A") (pintype "passive"))
      (node (ref "LED2") (pin "A") (pinfunction "A_A") (pintype "passive"))
      (node (ref "LED3") (pin "A") (pinfunction "A_A") (pintype "passive"))
      (node (ref "LED4") (pin "A") (pinfunction "A_A") (pintype "passive"))
      (node (ref "Q5") (pin "5") (pinfunction "D_5") (pintype "passive"))
      (node (ref "Q5") (pin "6") (pinfunction "D_6") (pintype "passive"))
      (node (ref "Q5") (pin "7") (pinfunction "D_7") (pintype "passive"))
      (node (ref "Q5") (pin "8") (pinfunction "D_8") (pintype "passive"))
      (node (ref "R38") (pin "2") (pinfunction "2_2") (pintype "passive"))
      (node (ref "R51") (pin "2") (pinfunction "2_2") (pintype "passive"))
      (node (ref "U1") (pin "2") (pinfunction "VDD_2") (pintype "passive"))
      (node (ref "U12") (pin "2") (pinfunction "VDD_2") (pintype "passive"))
      (node (ref "U13") (pin "2") (pinfunction "VDD_2") (pintype "passive"))
      (node (ref "U14") (pin "2") (pinfunction "VDD_2") (pintype "passive"))
      (node (ref "U15") (pin "2") (pinfunction "VDD_2") (pintype "passive"))
      (node (ref "U16") (pin "1") (pinfunction "VIN_1") (pintype "bidirectional"))
    )
    (net (code "2") (name "+15V") (class "Default")
      (node (ref "C36") (pin "1") (pinfunction "1_1") (pintype "passive"))
      (node (ref "J1") (pin "K") (pinfunction "12V_K") (pintype "bidirectional"))
      (node (ref "Q4") (pin "5") (pinfunction "D_5") (pintype "passive"))
      (node (ref "Q4") (pin "6") (pinfunction "D_6") (pintype "passive"))
      (node (ref "Q4") (pin "7") (pinfunction "D_7") (pintype "passive"))
      (node (ref "Q4") (pin "8") (pinfunction "D_8") (pintype "passive"))
      (node (ref "R33") (pin "1") (pinfunction "1_1") (pintype "passive"))
      (node (ref "R50") (pin "2") (pinfunction "2_2") (pintype "passive"))
      (node (ref "U11") (pin "4") (pinfunction "IN_4") (pintype "input"))
    )
    (net (code "3") (name "/ACCEL") (class "Default")
      (node (ref "C3") (pin "1") (pinfunction "1_1") (pintype "passive"))
      (node (ref "D3") (pin "3") (pinfunction "AC_3") (pintype "passive"))
      (node (ref "R8") (pin "1") (pinfunction "1_1") (pintype "passive"))
      (node (ref "U5") (pin "15") (pinfunction "PIO1_1_15") (pintype "bidirectional"))
    )
    (net (code "4") (name "/ACCEL_IO") (class "Default")
      (node (ref "J1") (pin "E") (pinfunction "ENG/ACC_E") (pintype "bidirectional"))
      (node (ref "R2") (pin "2") (pinfunction "2_2") (pintype "passive"))
      (node (ref "R8") (pin "2") (pinfunction "2_2") (pintype "passive"))
    )
    (net (code "5") (name "/ACC_INT") (class "Default")
      (node (ref "U5") (pin "2") (pinfunction "PIO0_24_2") (pintype "bidirectional"))
      (node (ref "U6") (pin "4") (pinfunction "INT1_4") (pintype "output"))
    )
    (net (code "6") (name "/ACC_SCL") (class "Default")
      (node (ref "R30") (pin "1") (pinfunction "1_1") (pintype "passive"))
      (node (ref "U5") (pin "3") (pinfunction "PIO0_25_3") (pintype "bidirectional"))
      (node (ref "U6") (pin "13") (pinfunction "SCL/SCLK_13") (pintype "bidirectional"))
    )
    (net (code "7") (name "/ACC_SDA") (class "Default")
      (node (ref "R31") (pin "1") (pinfunction "1_1") (pintype "passive"))
      (node (ref "U5") (pin "4") (pinfunction "PIO0_26_4") (pintype "bidirectional"))
      (node (ref "U6") (pin "14") (pinfunction "SDA/SDI_14") (pintype "bidirectional"))
    )
    (net (code "8") (name "/AD0.1") (class "Default")
      (node (ref "U10") (pin "6") (pinfunction "OUT_6") (pintype "output"))
      (node (ref "U5") (pin "19") (pinfunction "PIO1_5_19") (pintype "bidirectional"))
    )
    (net (code "9") (name "/AD0.2") (class "Default")
      (node (ref "U5") (pin "28") (pinfunction "PIO1_8_28") (pintype "bidirectional"))
      (node (ref "U9") (pin "6") (pinfunction "OUT_6") (pintype "output"))
    )
    (net (code "10") (name "/AD0.3") (class "Default")
      (node (ref "U5") (pin "27") (pinfunction "PIO1_7_27") (pintype "bidirectional"))
      (node (ref "U8") (pin "6") (pinfunction "OUT_6") (pintype "output"))
    )
    (net (code "11") (name "/CLUTCH") (class "Default")
      (node (ref "R37") (pin "1") (pinfunction "1_1") (pintype "passive"))
      (node (ref "U15") (pin "3") (pinfunction "IN_3") (pintype "passive"))
      (node (ref "U5") (pin "48") (pinfunction "PIO0_13_48") (pintype "bidirectional"))
    )
    (net (code "12") (name "/DM") (class "Default")
      (node (ref "J2") (pin "2") (pinfunction "2_2") (pintype "passive"))
      (node (ref "R27") (pin "1") (pinfunction "1_1") (pintype "passive"))
    )
    (net (code "13") (name "/DP") (class "Default")
      (node (ref "J2") (pin "3") (pinfunction "3_3") (pintype "passive"))
      (node (ref "R28") (pin "1") (pinfunction "1_1") (pintype "passive"))
    )
    (net (code "14") (name "/EXTRA") (class "Default")
      (node (ref "C5") (pin "1") (pinfunction "1_1") (pintype "passive"))
      (node (ref "R22") (pin "1") (pinfunction "1_1") (pintype "passive"))
      (node (ref "U2") (pin "4") (pinfunction "COL_4") (pintype "passive"))
      (node (ref "U5") (pin "12") (pinfunction "PIO0_30_12") (pintype "bidirectional"))
    )
    (net (code "15") (name "/EXTRA_IO") (class "Default")
      (node (ref "R4") (pin "1") (pinfunction "1_1") (pintype "passive"))
      (node (ref "R6") (pin "2") (pinfunction "2_2") (pintype "passive"))
    )
    (net (code "16") (name "/EXTRESET_N") (class "Default")
      (node (ref "J4") (pin "10") (pinfunction "10_10") (pintype "passive"))
      (node (ref "SW2") (pin "3") (pinfunction "3_3") (pintype "passive"))
      (node (ref "SW2") (pin "4") (pinfunction "4_4") (pintype "passive"))
      (node (ref "U7") (pin "4") (pinfunction "MR*_4") (pintype "bidirectional"))
    )
    (net (code "17") (name "/GPS_IO") (class "Default")
      (node (ref "J1") (pin "F") (pinfunction "GPS_F") (pintype "bidirectional"))
      (node (ref "U4") (pin "4") (pinfunction "RIN1_4") (pintype "passive"))
    )
    (net (code "18") (name "/GPS_RX") (class "Default")
      (node (ref "U4") (pin "19") (pinfunction "ROUT1_19") (pintype "passive"))
      (node (ref "U5") (pin "57") (pinfunction "PIO1_14_57") (pintype "bidirectional"))
    )
    (net (code "19") (name "/HORN") (class "Default")
      (node (ref "R21") (pin "1") (pinfunction "1_1") (pintype "passive"))
      (node (ref "U1") (pin "3") (pinfunction "IN_3") (pintype "passive"))
      (node (ref "U5") (pin "10") (pinfunction "PIO1_17_10") (pintype "bidirectional"))
    )
    (net (code "20") (name "/HORN_IO") (class "Default")
      (node (ref "CR1") (pin "2") (pinfunction "1_2") (pintype "passive"))
      (node (ref "J1") (pin "B") (pinfunction "HORN_B") (pintype "bidirectional"))
      (node (ref "Q1") (pin "5") (pinfunction "D_5") (pintype "passive"))
      (node (ref "Q1") (pin "6") (pinfunction "D_6") (pintype "passive"))
      (node (ref "Q1") (pin "7") (pinfunction "D_7") (pintype "passive"))
      (node (ref "Q1") (pin "8") (pinfunction "D_8") (pintype "passive"))
    )
    (net (code "21") (name "/ISP0") (class "Default")
      (node (ref "R11") (pin "1") (pinfunction "1_1") (pintype "passive"))
      (node (ref "SW1") (pin "1") (pinfunction "1_1") (pintype "passive"))
      (node (ref "SW1") (pin "2") (pinfunction "2_2") (pintype "passive"))
      (node (ref "U5") (pin "13") (pinfunction "PIO0_31_13") (pintype "bidirectional"))
    )
    (net (code "22") (name "/ISP1") (class "Default")
      (node (ref "R5") (pin "2") (pinfunction "2_2") (pintype "passive"))
      (node (ref "U5") (pin "38") (pinfunction "PIO0_4_38") (pintype "bidirectional"))
    )
    (net (code "23") (name "/ISP_RX") (class "Default")
      (node (ref "U4") (pin "15") (pinfunction "ROUT5_15") (pintype "passive"))
      (node (ref "U5") (pin "31") (pinfunction "PIO0_0_31") (pintype "bidirectional"))
    )
    (net (code "24") (name "/ISP_TX") (class "Default")
      (node (ref "U4") (pin "14") (pinfunction "DIN1_14") (pintype "passive"))
      (node (ref "U5") (pin "32") (pinfunction "PIO0_1_32") (pintype "bidirectional"))
    )
    (net (code "25") (name "/LED_A") (class "Default")
      (node (ref "R20") (pin "1") (pinfunction "1_1") (pintype "passive"))
      (node (ref "U5") (pin "29") (pinfunction "PIO1_9_29") (pintype "bidirectional"))
    )
    (net (code "26") (name "/LED_A_IO") (class "Default")
      (node (ref "J1") (pin "C") (pinfunction "LED_A_C") (pintype "bidirectional"))
      (node (ref "R14") (pin "2") (pinfunction "2_2") (pintype "passive"))
      (node (ref "R15") (pin "2") (pinfunction "2_2") (pintype "passive"))
    )
    (net (code "27") (name "/LED_E") (class "Default")
      (node (ref "R19") (pin "1") (pinfunction "1_1") (pintype "passive"))
      (node (ref "U5") (pin "30") (pinfunction "PIO1_10_30") (pintype "bidirectional"))
    )
    (net (code "28") (name "/LED_E_IO") (class "Default")
      (node (ref "J1") (pin "H") (pinfunction "LED_E_H") (pintype "bidirectional"))
      (node (ref "R12") (pin "2") (pinfunction "2_2") (pintype "passive"))
      (node (ref "R13") (pin "2") (pinfunction "2_2") (pintype "passive"))
    )
    (net (code "29") (name "/PH1SENSE") (class "Default")
      (node (ref "Q9") (pin "1") (pinfunction "S_1") (pintype "passive"))
      (node (ref "Q9") (pin "2") (pinfunction "S_2") (pintype "passive"))
      (node (ref "Q9") (pin "3") (pinfunction "S_3") (pintype "passive"))
      (node (ref "R49") (pin "2") (pinfunction "2_2") (pintype "passive"))
      (node (ref "U10") (pin "4") (pinfunction "IN+_4") (pintype "input"))
    )
    (net (code "30") (name "/PH2SENSE") (class "Default")
      (node (ref "Q8") (pin "1") (pinfunction "S_1") (pintype "passive"))
      (node (ref "Q8") (pin "2") (pinfunction "S_2") (pintype "passive"))
      (node (ref "Q8") (pin "3") (pinfunction "S_3") (pintype "passive"))
      (node (ref "R47") (pin "2") (pinfunction "2_2") (pintype "passive"))
      (node (ref "U9") (pin "4") (pinfunction "IN+_4") (pintype "input"))
    )
    (net (code "31") (name "/PH3SENSE") (class "Default")
      (node (ref "Q7") (pin "1") (pinfunction "S_1") (pintype "passive"))
      (node (ref "Q7") (pin "2") (pinfunction "S_2") (pintype "passive"))
      (node (ref "Q7") (pin "3") (pinfunction "S_3") (pintype "passive"))
      (node (ref "R46") (pin "2") (pinfunction "2_2") (pintype "passive"))
      (node (ref "U8") (pin "4") (pinfunction "IN+_4") (pintype "input"))
    )
    (net (code "32") (name "/PHASE1") (class "Default")
      (node (ref "R34") (pin "1") (pinfunction "1_1") (pintype "passive"))
      (node (ref "U12") (pin "3") (pinfunction "IN_3") (pintype "passive"))
      (node (ref "U5") (pin "41") (pinfunction "PIO0_7_41") (pintype "bidirectional"))
    )
    (net (code "33") (name "/PHASE2") (class "Default")
      (node (ref "R35") (pin "1") (pinfunction "1_1") (pintype "passive"))
      (node (ref "U13") (pin "3") (pinfunction "IN_3") (pintype "passive"))
      (node (ref "U5") (pin "43") (pinfunction "PIO0_8_43") (pintype "bidirectional"))
    )
    (net (code "34") (name "/PHASE3") (class "Default")
      (node (ref "R36") (pin "1") (pinfunction "1_1") (pintype "passive"))
      (node (ref "U14") (pin "3") (pinfunction "IN_3") (pintype "passive"))
      (node (ref "U5") (pin "45") (pinfunction "PIO0_10_45") (pintype "bidirectional"))
    )
    (net (code "35") (name "/RESETLED") (class "Default")
      (node (ref "R53") (pin "2") (pinfunction "2_2") (pintype "passive"))
      (node (ref "U7") (pin "3") (pinfunction "RST_3") (pintype "bidirectional"))
    )
    (net (code "36") (name "/RESET_N") (class "Default")
      (node (ref "R32") (pin "2") (pinfunction "2_2") (pintype "passive"))
      (node (ref "U5") (pin "64") (pinfunction "RESET_64") (pintype "input"))
      (node (ref "U7") (pin "1") (pinfunction "RST*_1") (pintype "bidirectional"))
    )
    (net (code "37") (name "/RXD0_232") (class "Default")
      (node (ref "J3") (pin "2") (pinfunction "2_2") (pintype "passive"))
      (node (ref "R13") (pin "1") (pinfunction "1_1") (pintype "passive"))
      (node (ref "U4") (pin "8") (pinfunction "RIN5_8") (pintype "passive"))
    )
    (net (code "38") (name "/RXD1") (class "Default")
      (node (ref "U4") (pin "17") (pinfunction "ROUT3_17") (pintype "passive"))
      (node (ref "U5") (pin "39") (pinfunction "PIO0_5_39") (pintype "bidirectional"))
    )
    (net (code "39") (name "/RXD1_232") (class "Default")
      (node (ref "J3") (pin "5") (pinfunction "5_5") (pintype "passive"))
      (node (ref "U4") (pin "6") (pinfunction "RIN3_6") (pintype "passive"))
    )
    (net (code "40") (name "/SPEED") (class "Default")
      (node (ref "C4") (pin "1") (pinfunction "1_1") (pintype "passive"))
      (node (ref "D4") (pin "3") (pinfunction "AC_3") (pintype "passive"))
      (node (ref "R9") (pin "1") (pinfunction "1_1") (pintype "passive"))
      (node (ref "U5") (pin "14") (pinfunction "PIO1_0_14") (pintype "bidirectional"))
    )
    (net (code "41") (name "/SPEED_IO") (class "Default")
      (node (ref "J1") (pin "D") (pinfunction "ARM/SPD_D") (pintype "bidirectional"))
      (node (ref "R3") (pin "2") (pinfunction "2_2") (pintype "passive"))
      (node (ref "R9") (pin "2") (pinfunction "2_2") (pintype "passive"))
    )
    (net (code "42") (name "/STATUS_0") (class "Default")
      (node (ref "R55") (pin "2") (pinfunction "2_2") (pintype "passive"))
      (node (ref "U5") (pin "63") (pinfunction "PIO0_22_63") (pintype "bidirectional"))
    )
    (net (code "43") (name "/STATUS_1") (class "Default")
      (node (ref "R56") (pin "2") (pinfunction "2_2") (pintype "passive"))
      (node (ref "U5") (pin "62") (pinfunction "PIO1_15_62") (pintype "bidirectional"))
    )
    (net (code "44") (name "/STATUS_2") (class "Default")
      (node (ref "R57") (pin "2") (pinfunction "2_2") (pintype "passive"))
      (node (ref "U5") (pin "61") (pinfunction "PIO0_21_61") (pintype "bidirectional"))
    )
    (net (code "45") (name "/STATUS_3") (class "Default")
      (node (ref "R58") (pin "2") (pinfunction "2_2") (pintype "passive"))
      (node (ref "U5") (pin "60") (pinfunction "PIO0_20_60") (pintype "bidirectional"))
    )
    (net (code "46") (name "/STATUS_4") (class "Default")
      (node (ref "R59") (pin "2") (pinfunction "2_2") (pintype "passive"))
      (node (ref "U5") (pin "59") (pinfunction "PIO0_19_59") (pintype "bidirectional"))
    )
    (net (code "47") (name "/STATUS_5") (class "Default")
      (node (ref "R60") (pin "2") (pinfunction "2_2") (pintype "passive"))
      (node (ref "U5") (pin "58") (pinfunction "PIO0_18_58") (pintype "bidirectional"))
    )
    (net (code "48") (name "/STATUS_6") (class "Default")
      (node (ref "R61") (pin "2") (pinfunction "2_2") (pintype "passive"))
      (node (ref "U5") (pin "54") (pinfunction "PIO1_13_54") (pintype "bidirectional"))
    )
    (net (code "49") (name "/STATUS_7") (class "Default")
      (node (ref "R62") (pin "2") (pinfunction "2_2") (pintype "passive"))
      (node (ref "U5") (pin "51") (pinfunction "PIO1_12_51") (pintype "bidirectional"))
    )
    (net (code "50") (name "/SWDCLK") (class "Default")
      (node (ref "J4") (pin "4") (pinfunction "4_4") (pintype "passive"))
      (node (ref "U5") (pin "52") (pinfunction "SWCLK/PIO0_16_52") (pintype "bidirectional"))
    )
    (net (code "51") (name "/SWDIO") (class "Default")
      (node (ref "J4") (pin "2") (pinfunction "2_2") (pintype "passive"))
      (node (ref "U5") (pin "53") (pinfunction "SWDIO/PIO0_17_53") (pintype "bidirectional"))
    )
    (net (code "52") (name "/SWO") (class "Default")
      (node (ref "J4") (pin "6") (pinfunction "6_6") (pintype "passive"))
      (node (ref "U5") (pin "50") (pinfunction "PIO0_15_50") (pintype "bidirectional"))
    )
    (net (code "53") (name "/TACH") (class "Default")
      (node (ref "C6") (pin "1") (pinfunction "1_1") (pintype "passive"))
      (node (ref "R23") (pin "1") (pinfunction "1_1") (pintype "passive"))
      (node (ref "U3") (pin "4") (pinfunction "COL_4") (pintype "passive"))
      (node (ref "U5") (pin "1") (pinfunction "PIO0_23_1") (pintype "bidirectional"))
      (node (ref "U5") (pin "18") (pinfunction "PIO1_4_18") (pintype "bidirectional"))
    )
    (net (code "54") (name "/TACH_IO") (class "Default")
      (node (ref "J1") (pin "J") (pinfunction "TACH_J") (pintype "bidirectional"))
      (node (ref "R16") (pin "2") (pinfunction "2_2") (pintype "passive"))
    )
    (net (code "55") (name "/TRANS") (class "Default")
      (node (ref "C2") (pin "1") (pinfunction "1_1") (pintype "passive"))
      (node (ref "R18") (pin "1") (pinfunction "1_1") (pintype "passive"))
      (node (ref "U5") (pin "16") (pinfunction "PIO1_2_16") (pintype "bidirectional"))
    )
    (net (code "56") (name "/TRANS_IO") (class "Default")
      (node (ref "J1") (pin "G") (pinfunction "TRANS_G") (pintype "bidirectional"))
      (node (ref "R1") (pin "2") (pinfunction "2_2") (pintype "passive"))
      (node (ref "R7") (pin "2") (pinfunction "2_2") (pintype "passive"))
    )
    (net (code "57") (name "/TXD0_232") (class "Default")
      (node (ref "J3") (pin "1") (pinfunction "1_1") (pintype "passive"))
      (node (ref "R15") (pin "1") (pinfunction "1_1") (pintype "passive"))
      (node (ref "U4") (pin "9") (pinfunction "DOUT1_9") (pintype "passive"))
    )
    (net (code "58") (name "/TXD1") (class "Default")
      (node (ref "U4") (pin "12") (pinfunction "DIN3_12") (pintype "passive"))
      (node (ref "U5") (pin "40") (pinfunction "PIO0_6_40") (pintype "bidirectional"))
    )
    (net (code "59") (name "/TXD1_232") (class "Default")
      (node (ref "J3") (pin "6") (pinfunction "6_6") (pintype "passive"))
      (node (ref "U4") (pin "11") (pinfunction "DOUT3_11") (pintype "passive"))
    )
    (net (code "60") (name "/USB_DM") (class "Default")
      (node (ref "R27") (pin "2") (pinfunction "2_2") (pintype "passive"))
      (node (ref "U5") (pin "6") (pinfunction "USB_DM_6") (pintype "bidirectional"))
    )
    (net (code "61") (name "/USB_DP") (class "Default")
      (node (ref "R28") (pin "2") (pinfunction "2_2") (pintype "passive"))
      (node (ref "U5") (pin "5") (pinfunction "USB_DP_5") (pintype "bidirectional"))
    )
    (net (code "62") (name "/USB_UP_LED") (class "Default")
      (node (ref "R54") (pin "2") (pinfunction "2_2") (pintype "passive"))
      (node (ref "U5") (pin "17") (pinfunction "PIO1_3_17") (pintype "bidirectional"))
    )
    (net (code "63") (name "/USB_VBUS") (class "Default")
      (node (ref "C7") (pin "1") (pinfunction "1_1") (pintype "passive"))
      (node (ref "R24") (pin "2") (pinfunction "2_2") (pintype "passive"))
      (node (ref "R26") (pin "1") (pinfunction "1_1") (pintype "passive"))
      (node (ref "U5") (pin "26") (pinfunction "PIO1_6_26") (pintype "bidirectional"))
    )
    (net (code "64") (name "/VBUS") (class "Default")
      (node (ref "J2") (pin "1") (pinfunction "1_1") (pintype "passive"))
      (node (ref "R26") (pin "2") (pinfunction "2_2") (pintype "passive"))
    )
    (net (code "65") (name "3.3V") (class "Default")
      (node (ref "C12") (pin "1") (pinfunction "1_1") (pintype "passive"))
      (node (ref "C17") (pin "1") (pinfunction "1_1") (pintype "passive"))
      (node (ref "C18") (pin "1") (pinfunction "1_1") (pintype "passive"))
      (node (ref "C19") (pin "1") (pinfunction "1_1") (pintype "passive"))
      (node (ref "C20") (pin "1") (pinfunction "1_1") (pintype "passive"))
      (node (ref "C21") (pin "1") (pinfunction "1_1") (pintype "passive"))
      (node (ref "C23") (pin "1") (pinfunction "1_1") (pintype "passive"))
      (node (ref "C24") (pin "1") (pinfunction "1_1") (pintype "passive"))
      (node (ref "C25") (pin "1") (pinfunction "1_1") (pintype "passive"))
      (node (ref "C26") (pin "1") (pinfunction "1_1") (pintype "passive"))
      (node (ref "C27") (pin "1") (pinfunction "1_1") (pintype "passive"))
      (node (ref "C28") (pin "1") (pinfunction "1_1") (pintype "passive"))
      (node (ref "C29") (pin "1") (pinfunction "1_1") (pintype "passive"))
      (node (ref "C30") (pin "2") (pinfunction "2_2") (pintype "passive"))
      (node (ref "C31") (pin "2") (pinfunction "2_2") (pintype "passive"))
      (node (ref "C32") (pin "2") (pinfunction "2_2") (pintype "passive"))
      (node (ref "C33") (pin "2") (pinfunction "2_2") (pintype "passive"))
      (node (ref "C34") (pin "2") (pinfunction "2_2") (pintype "passive"))
      (node (ref "C35") (pin "2") (pinfunction "2_2") (pintype "passive"))
      (node (ref "C45") (pin "1") (pinfunction "1_1") (pintype "passive"))
      (node (ref "C46") (pin "1") (pinfunction "1_1") (pintype "passive"))
      (node (ref "C47") (pin "1") (pinfunction "1_1") (pintype "passive"))
      (node (ref "C48") (pin "1") (pinfunction "1_1") (pintype "passive"))
      (node (ref "C49") (pin "1") (pinfunction "1_1") (pintype "passive"))
      (node (ref "C50") (pin "1") (pinfunction "1_1") (pintype "passive"))
      (node (ref "C51") (pin "1") (pinfunction "1_1") (pintype "passive"))
      (node (ref "D2") (pin "2") (pinfunction "C_2") (pintype "passive"))
      (node (ref "D3") (pin "2") (pinfunction "C_2") (pintype "passive"))
      (node (ref "D4") (pin "2") (pinfunction "C_2") (pintype "passive"))
      (node (ref "J4") (pin "1") (pinfunction "1_1") (pintype "passive"))
      (node (ref "R1") (pin "1") (pinfunction "1_1") (pintype "passive"))
      (node (ref "R11") (pin "2") (pinfunction "2_2") (pintype "passive"))
      (node (ref "R2") (pin "1") (pinfunction "1_1") (pintype "passive"))
      (node (ref "R22") (pin "2") (pinfunction "2_2") (pintype "passive"))
      (node (ref "R23") (pin "2") (pinfunction "2_2") (pintype "passive"))
      (node (ref "R29") (pin "1") (pinfunction "1_1") (pintype "passive"))
      (node (ref "R3") (pin "1") (pinfunction "1_1") (pintype "passive"))
      (node (ref "R30") (pin "2") (pinfunction "2_2") (pintype "passive"))
      (node (ref "R31") (pin "2") (pinfunction "2_2") (pintype "passive"))
      (node (ref "R32") (pin "1") (pinfunction "1_1") (pintype "passive"))
      (node (ref "R5") (pin "1") (pinfunction "1_1") (pintype "passive"))
      (node (ref "R52") (pin "2") (pinfunction "2_2") (pintype "passive"))
      (node (ref "R63") (pin "2") (pinfunction "2_2") (pintype "passive"))
      (node (ref "U10") (pin "3") (pinfunction "V+_3") (pintype "power_in"))
      (node (ref "U16") (pin "3") (pinfunction "VOUT_3") (pintype "bidirectional"))
      (node (ref "U4") (pin "22") (pinfunction "*FORCEOFF_22") (pintype "passive"))
      (node (ref "U4") (pin "26") (pinfunction "VCC_26") (pintype "passive"))
      (node (ref "U5") (pin "24") (pinfunction "VDD_3_24") (pintype "power_in"))
      (node (ref "U5") (pin "34") (pinfunction "VDD_4_34") (pintype "power_in"))
      (node (ref "U5") (pin "56") (pinfunction "VDD_56") (pintype "power_in"))
      (node (ref "U5") (pin "8") (pinfunction "VDD_2_8") (pintype "power_in"))
      (node (ref "U6") (pin "1") (pinfunction "AD0/SDO_1") (pintype "bidirectional"))
      (node (ref "U6") (pin "12") (pinfunction "~{CS}_12") (pintype "input"))
      (node (ref "U6") (pin "5") (pinfunction "VDDIO_5") (pintype "power_in"))
      (node (ref "U6") (pin "8") (pinfunction "VDD_8") (pintype "power_in"))
      (node (ref "U7") (pin "5") (pinfunction "VDD_5") (pintype "bidirectional"))
      (node (ref "U8") (pin "3") (pinfunction "V+_3") (pintype "power_in"))
      (node (ref "U9") (pin "3") (pinfunction "V+_3") (pintype "power_in"))
    )
    (net (code "66") (name "AGND") (class "Default")
      (node (ref "C10") (pin "1") (pinfunction "1_1") (pintype "passive"))
      (node (ref "C11") (pin "1") (pinfunction "1_1") (pintype "passive"))
      (node (ref "C15") (pin "2") (pinfunction "2_2") (pintype "passive"))
      (node (ref "C16") (pin "2") (pinfunction "2_2") (pintype "passive"))
      (node (ref "SUPPLY1") (pin "P$1") (pinfunction "P$1_P$1") (pintype "bidirectional"))
      (node (ref "U5") (pin "20") (pinfunction "VSSA_20") (pintype "power_in"))
      (node (ref "U5") (pin "21") (pinfunction "VREFN_21") (pintype "power_in"))
    )
    (net (code "67") (name "GND") (class "Default")
      (node (ref "C12") (pin "2") (pinfunction "2_2") (pintype "passive"))
      (node (ref "C13") (pin "2") (pinfunction "2_2") (pintype "passive"))
      (node (ref "C14") (pin "2") (pinfunction "2_2") (pintype "passive"))
      (node (ref "C17") (pin "2") (pinfunction "2_2") (pintype "passive"))
      (node (ref "C18") (pin "2") (pinfunction "2_2") (pintype "passive"))
      (node (ref "C19") (pin "2") (pinfunction "2_2") (pintype "passive"))
      (node (ref "C2") (pin "2") (pinfunction "2_2") (pintype "passive"))
      (node (ref "C20") (pin "2") (pinfunction "2_2") (pintype "passive"))
      (node (ref "C21") (pin "2") (pinfunction "2_2") (pintype "passive"))
      (node (ref "C22") (pin "2") (pinfunction "2_2") (pintype "passive"))
      (node (ref "C23") (pin "2") (pinfunction "2_2") (pintype "passive"))
      (node (ref "C24") (pin "2") (pinfunction "2_2") (pintype "passive"))
      (node (ref "C25") (pin "2") (pinfunction "2_2") (pintype "passive"))
      (node (ref "C26") (pin "2") (pinfunction "2_2") (pintype "passive"))
      (node (ref "C27") (pin "2") (pinfunction "2_2") (pintype "passive"))
      (node (ref "C28") (pin "2") (pinfunction "2_2") (pintype "passive"))
      (node (ref "C29") (pin "2") (pinfunction "2_2") (pintype "passive"))
      (node (ref "C3") (pin "2") (pinfunction "2_2") (pintype "passive"))
      (node (ref "C30") (pin "1") (pinfunction "1_1") (pintype "passive"))
      (node (ref "C31") (pin "1") (pinfunction "1_1") (pintype "passive"))
      (node (ref "C32") (pin "1") (pinfunction "1_1") (pintype "passive"))
      (node (ref "C33") (pin "1") (pinfunction "1_1") (pintype "passive"))
      (node (ref "C34") (pin "1") (pinfunction "1_1") (pintype "passive"))
      (node (ref "C35") (pin "1") (pinfunction "1_1") (pintype "passive"))
      (node (ref "C4") (pin "2") (pinfunction "2_2") (pintype "passive"))
      (node (ref "C43") (pin "2") (pinfunction "2_2") (pintype "passive"))
      (node (ref "C44") (pin "2") (pinfunction "2_2") (pintype "passive"))
      (node (ref "C45") (pin "2") (pinfunction "2_2") (pintype "passive"))
      (node (ref "C46") (pin "2") (pinfunction "2_2") (pintype "passive"))
      (node (ref "C47") (pin "2") (pinfunction "2_2") (pintype "passive"))
      (node (ref "C48") (pin "2") (pinfunction "2_2") (pintype "passive"))
      (node (ref "C49") (pin "2") (pinfunction "2_2") (pintype "passive"))
      (node (ref "C5") (pin "2") (pinfunction "2_2") (pintype "passive"))
      (node (ref "C50") (pin "2") (pinfunction "2_2") (pintype "passive"))
      (node (ref "C51") (pin "2") (pinfunction "2_2") (pintype "passive"))
      (node (ref "C6") (pin "2") (pinfunction "2_2") (pintype "passive"))
      (node (ref "C7") (pin "2") (pinfunction "2_2") (pintype "passive"))
      (node (ref "D2") (pin "1") (pinfunction "A_1") (pintype "passive"))
      (node (ref "D3") (pin "1") (pinfunction "A_1") (pintype "passive"))
      (node (ref "D4") (pin "1") (pinfunction "A_1") (pintype "passive"))
      (node (ref "J2") (pin "5") (pinfunction "5_5") (pintype "passive"))
      (node (ref "J2") (pin "SH1") (pinfunction "SHIELD_SH1") (pintype "passive"))
      (node (ref "J2") (pin "SH2") (pinfunction "SHIELD_SH2") (pintype "passive"))
      (node (ref "J2") (pin "SH3") (pinfunction "SHIELD_SH3") (pintype "passive"))
      (node (ref "J2") (pin "SH4") (pinfunction "SHIELD_SH4") (pintype "passive"))
      (node (ref "J2") (pin "SH5") (pinfunction "SHIELD_SH5") (pintype "passive"))
      (node (ref "J2") (pin "SH6") (pinfunction "SHIELD_SH6") (pintype "passive"))
      (node (ref "J2") (pin "SH7") (pinfunction "SHIELD_SH7") (pintype "passive"))
      (node (ref "J2") (pin "SH8") (pinfunction "SHIELD_SH8") (pintype "passive"))
      (node (ref "J3") (pin "3") (pinfunction "3_3") (pintype "passive"))
      (node (ref "J3") (pin "4") (pinfunction "4_4") (pintype "passive"))
      (node (ref "J4") (pin "3") (pinfunction "3_3") (pintype "passive"))
      (node (ref "J4") (pin "5") (pinfunction "5_5") (pintype "passive"))
      (node (ref "J4") (pin "9") (pinfunction "9_9") (pintype "passive"))
      (node (ref "LED10") (pin "C") (pinfunction "C_C") (pintype "passive"))
      (node (ref "LED11") (pin "C") (pinfunction "C_C") (pintype "passive"))
      (node (ref "LED12") (pin "C") (pinfunction "C_C") (pintype "passive"))
      (node (ref "LED13") (pin "C") (pinfunction "C_C") (pintype "passive"))
      (node (ref "LED14") (pin "C") (pinfunction "C_C") (pintype "passive"))
      (node (ref "LED15") (pin "C") (pinfunction "C_C") (pintype "passive"))
      (node (ref "LED16") (pin "C") (pinfunction "C_C") (pintype "passive"))
      (node (ref "LED17") (pin "C") (pinfunction "C_C") (pintype "passive"))
      (node (ref "LED7") (pin "C") (pinfunction "C_C") (pintype "passive"))
      (node (ref "LED8") (pin "C") (pinfunction "C_C") (pintype "passive"))
      (node (ref "LED9") (pin "C") (pinfunction "C_C") (pintype "passive"))
      (node (ref "Q2") (pin "2") (pinfunction "E_2") (pintype "passive"))
      (node (ref "Q3") (pin "2") (pinfunction "E_2") (pintype "passive"))
      (node (ref "R21") (pin "2") (pinfunction "2_2") (pintype "passive"))
      (node (ref "R25") (pin "1") (pinfunction "1_1") (pintype "passive"))
      (node (ref "SUPPLY1") (pin "P$2") (pinfunction "P$2_P$2") (pintype "bidirectional"))
      (node (ref "SUPPLY2") (pin "P$2") (pinfunction "P$2_P$2") (pintype "bidirectional"))
      (node (ref "SW1") (pin "3") (pinfunction "3_3") (pintype "passive"))
      (node (ref "SW1") (pin "4") (pinfunction "4_4") (pintype "passive"))
      (node (ref "SW2") (pin "1") (pinfunction "1_1") (pintype "passive"))
      (node (ref "SW2") (pin "2") (pinfunction "2_2") (pintype "passive"))
      (node (ref "U10") (pin "1") (pinfunction "REF_1") (pintype "power_in"))
      (node (ref "U10") (pin "2") (pinfunction "GND_2") (pintype "power_in"))
      (node (ref "U16") (pin "2") (pinfunction "GND_2") (pintype "bidirectional"))
      (node (ref "U16") (pin "TAB") (pinfunction "GND_TAB") (pintype "bidirectional"))
      (node (ref "U2") (pin "3") (pinfunction "EMIT_3") (pintype "passive"))
      (node (ref "U3") (pin "3") (pinfunction "EMIT_3") (pintype "passive"))
      (node (ref "U4") (pin "23") (pinfunction "FORCEON_23") (pintype "passive"))
      (node (ref "U4") (pin "25") (pinfunction "GND_25") (pintype "passive"))
      (node (ref "U5") (pin "25") (pinfunction "VSS_3_25") (pintype "power_in"))
      (node (ref "U5") (pin "33") (pinfunction "RTCXIN_33") (pintype "input"))
      (node (ref "U5") (pin "55") (pinfunction "VSS_55") (pintype "power_in"))
      (node (ref "U5") (pin "9") (pinfunction "VSS_2_9") (pintype "power_in"))
      (node (ref "U6") (pin "6") (pinfunction "GND_6") (pintype "power_in"))
      (node (ref "U6") (pin "7") (pinfunction "RESV_7") (pintype "power_in"))
      (node (ref "U7") (pin "2") (pinfunction "VSS_2") (pintype "bidirectional"))
      (node (ref "U8") (pin "1") (pinfunction "REF_1") (pintype "power_in"))
      (node (ref "U8") (pin "2") (pinfunction "GND_2") (pintype "power_in"))
      (node (ref "U9") (pin "1") (pinfunction "REF_1") (pintype "power_in"))
      (node (ref "U9") (pin "2") (pinfunction "GND_2") (pintype "power_in"))
    )
    (net (code "68") (name "GNDIO") (class "Default")
      (node (ref "C1") (pin "2") (pinfunction "2_2") (pintype "passive"))
      (node (ref "C36") (pin "2") (pinfunction "2_2") (pintype "passive"))
      (node (ref "C38") (pin "2") (pinfunction "2_2") (pintype "passive"))
      (node (ref "C39") (pin "2") (pinfunction "2_2") (pintype "passive"))
      (node (ref "C40") (pin "2") (pinfunction "2_2") (pintype "passive"))
      (node (ref "C41") (pin "2") (pinfunction "2_2") (pintype "passive"))
      (node (ref "C42") (pin "2") (pinfunction "2_2") (pintype "passive"))
      (node (ref "CR1") (pin "1") (pinfunction "2_1") (pintype "passive"))
      (node (ref "D1") (pin "1") (pinfunction "A_1") (pintype "passive"))
      (node (ref "J1") (pin "A") (pinfunction "GND_A") (pintype "bidirectional"))
      (node (ref "LED5") (pin "C") (pinfunction "C_C") (pintype "passive"))
      (node (ref "LED6") (pin "C") (pinfunction "C_C") (pintype "passive"))
      (node (ref "Q1") (pin "1") (pinfunction "S_1") (pintype "passive"))
      (node (ref "Q1") (pin "2") (pinfunction "S_2") (pintype "passive"))
      (node (ref "Q1") (pin "3") (pinfunction "S_3") (pintype "passive"))
      (node (ref "Q6") (pin "1") (pinfunction "S_1") (pintype "passive"))
      (node (ref "Q6") (pin "2") (pinfunction "S_2") (pintype "passive"))
      (node (ref "Q6") (pin "3") (pinfunction "S_3") (pintype "passive"))
      (node (ref "R34") (pin "2") (pinfunction "2_2") (pintype "passive"))
      (node (ref "R35") (pin "2") (pinfunction "2_2") (pintype "passive"))
      (node (ref "R36") (pin "2") (pinfunction "2_2") (pintype "passive"))
      (node (ref "R37") (pin "2") (pinfunction "2_2") (pintype "passive"))
      (node (ref "R4") (pin "2") (pinfunction "2_2") (pintype "passive"))
      (node (ref "R46") (pin "1") (pinfunction "1_1") (pintype "passive"))
      (node (ref "R47") (pin "1") (pinfunction "1_1") (pintype "passive"))
      (node (ref "R49") (pin "1") (pinfunction "1_1") (pintype "passive"))
      (node (ref "SUPPLY2") (pin "P$1") (pinfunction "P$1_P$1") (pintype "bidirectional"))
      (node (ref "U1") (pin "4") (pinfunction "GND_4") (pintype "passive"))
      (node (ref "U10") (pin "5") (pinfunction "IN-_5") (pintype "input"))
      (node (ref "U11") (pin "6") (pinfunction "GND_6") (pintype "power_in"))
      (node (ref "U12") (pin "4") (pinfunction "GND_4") (pintype "passive"))
      (node (ref "U13") (pin "4") (pinfunction "GND_4") (pintype "passive"))
      (node (ref "U14") (pin "4") (pinfunction "GND_4") (pintype "passive"))
      (node (ref "U15") (pin "4") (pinfunction "GND_4") (pintype "passive"))
      (node (ref "U2") (pin "2") (pinfunction "C_2") (pintype "passive"))
      (node (ref "U3") (pin "2") (pinfunction "C_2") (pintype "passive"))
      (node (ref "U8") (pin "5") (pinfunction "IN-_5") (pintype "input"))
      (node (ref "U9") (pin "5") (pinfunction "IN-_5") (pintype "input"))
    )
    (net (code "69") (name "Net-(D1-AC)") (class "Default")
      (node (ref "D1") (pin "3") (pinfunction "AC_3") (pintype "passive"))
      (node (ref "R17") (pin "2") (pinfunction "2_2") (pintype "passive"))
      (node (ref "R6") (pin "1") (pinfunction "1_1") (pintype "passive"))
    )
    (net (code "70") (name "Net-(D2-AC)") (class "Default")
      (node (ref "D2") (pin "3") (pinfunction "AC_3") (pintype "passive"))
      (node (ref "R18") (pin "2") (pinfunction "2_2") (pintype "passive"))
      (node (ref "R7") (pin "1") (pinfunction "1_1") (pintype "passive"))
    )
    (net (code "71") (name "Net-(J5-CLUTCH2)") (class "Default")
      (node (ref "D6") (pin "A") (pinfunction "A_A") (pintype "passive"))
      (node (ref "J5") (pin "6") (pinfunction "CLUTCH2_6") (pintype "bidirectional"))
      (node (ref "Q6") (pin "5") (pinfunction "D_5") (pintype "passive"))
      (node (ref "Q6") (pin "6") (pinfunction "D_6") (pintype "passive"))
      (node (ref "Q6") (pin "7") (pinfunction "D_7") (pintype "passive"))
      (node (ref "Q6") (pin "8") (pinfunction "D_8") (pintype "passive"))
      (node (ref "R43") (pin "1") (pinfunction "1_1") (pintype "passive"))
    )
    (net (code "72") (name "Net-(J5-PHA1)") (class "Default")
      (node (ref "D9") (pin "A") (pinfunction "A_A") (pintype "passive"))
      (node (ref "J5") (pin "2") (pinfunction "PHA1_2") (pintype "bidirectional"))
      (node (ref "Q9") (pin "5") (pinfunction "D_5") (pintype "passive"))
      (node (ref "Q9") (pin "6") (pinfunction "D_6") (pintype "passive"))
      (node (ref "Q9") (pin "7") (pinfunction "D_7") (pintype "passive"))
      (node (ref "Q9") (pin "8") (pinfunction "D_8") (pintype "passive"))
      (node (ref "R48") (pin "1") (pinfunction "1_1") (pintype "passive"))
    )
    (net (code "73") (name "Net-(J5-PHA2)") (class "Default")
      (node (ref "D8") (pin "A") (pinfunction "A_A") (pintype "passive"))
      (node (ref "J5") (pin "3") (pinfunction "PHA2_3") (pintype "bidirectional"))
      (node (ref "Q8") (pin "5") (pinfunction "D_5") (pintype "passive"))
      (node (ref "Q8") (pin "6") (pinfunction "D_6") (pintype "passive"))
      (node (ref "Q8") (pin "7") (pinfunction "D_7") (pintype "passive"))
      (node (ref "Q8") (pin "8") (pinfunction "D_8") (pintype "passive"))
      (node (ref "R45") (pin "1") (pinfunction "1_1") (pintype "passive"))
    )
    (net (code "74") (name "Net-(J5-PHA3)") (class "Default")
      (node (ref "D7") (pin "A") (pinfunction "A_A") (pintype "passive"))
      (node (ref "J5") (pin "4") (pinfunction "PHA3_4") (pintype "bidirectional"))
      (node (ref "Q7") (pin "5") (pinfunction "D_5") (pintype "passive"))
      (node (ref "Q7") (pin "6") (pinfunction "D_6") (pintype "passive"))
      (node (ref "Q7") (pin "7") (pinfunction "D_7") (pintype "passive"))
      (node (ref "Q7") (pin "8") (pinfunction "D_8") (pintype "passive"))
      (node (ref "R44") (pin "1") (pinfunction "1_1") (pintype "passive"))
    )
    (net (code "75") (name "Net-(LED1-PadC)") (class "Default")
      (node (ref "LED1") (pin "C") (pinfunction "C_C") (pintype "passive"))
      (node (ref "R43") (pin "2") (pinfunction "2_2") (pintype "passive"))
    )
    (net (code "76") (name "Net-(LED2-PadC)") (class "Default")
      (node (ref "LED2") (pin "C") (pinfunction "C_C") (pintype "passive"))
      (node (ref "R44") (pin "2") (pinfunction "2_2") (pintype "passive"))
    )
    (net (code "77") (name "Net-(LED3-PadC)") (class "Default")
      (node (ref "LED3") (pin "C") (pinfunction "C_C") (pintype "passive"))
      (node (ref "R45") (pin "2") (pinfunction "2_2") (pintype "passive"))
    )
    (net (code "78") (name "Net-(LED4-PadC)") (class "Default")
      (node (ref "LED4") (pin "C") (pinfunction "C_C") (pintype "passive"))
      (node (ref "R48") (pin "2") (pinfunction "2_2") (pintype "passive"))
    )
    (net (code "79") (name "Net-(LED5-PadA)") (class "Default")
      (node (ref "LED5") (pin "A") (pinfunction "A_A") (pintype "passive"))
      (node (ref "R50") (pin "1") (pinfunction "1_1") (pintype "passive"))
    )
    (net (code "80") (name "Net-(LED6-PadA)") (class "Default")
      (node (ref "LED6") (pin "A") (pinfunction "A_A") (pintype "passive"))
      (node (ref "R51") (pin "1") (pinfunction "1_1") (pintype "passive"))
    )
    (net (code "81") (name "Net-(LED7-PadA)") (class "Default")
      (node (ref "LED7") (pin "A") (pinfunction "A_A") (pintype "passive"))
      (node (ref "R52") (pin "1") (pinfunction "1_1") (pintype "passive"))
    )
    (net (code "82") (name "Net-(LED8-PadA)") (class "Default")
      (node (ref "LED8") (pin "A") (pinfunction "A_A") (pintype "passive"))
      (node (ref "R53") (pin "1") (pinfunction "1_1") (pintype "passive"))
    )
    (net (code "83") (name "Net-(LED9-PadA)") (class "Default")
      (node (ref "LED9") (pin "A") (pinfunction "A_A") (pintype "passive"))
      (node (ref "R54") (pin "1") (pinfunction "1_1") (pintype "passive"))
    )
    (net (code "84") (name "Net-(LED10-PadA)") (class "Default")
      (node (ref "LED10") (pin "A") (pinfunction "A_A") (pintype "passive"))
      (node (ref "R55") (pin "1") (pinfunction "1_1") (pintype "passive"))
    )
    (net (code "85") (name "Net-(LED11-PadA)") (class "Default")
      (node (ref "LED11") (pin "A") (pinfunction "A_A") (pintype "passive"))
      (node (ref "R56") (pin "1") (pinfunction "1_1") (pintype "passive"))
    )
    (net (code "86") (name "Net-(LED12-PadA)") (class "Default")
      (node (ref "LED12") (pin "A") (pinfunction "A_A") (pintype "passive"))
      (node (ref "R57") (pin "1") (pinfunction "1_1") (pintype "passive"))
    )
    (net (code "87") (name "Net-(LED13-PadA)") (class "Default")
      (node (ref "LED13") (pin "A") (pinfunction "A_A") (pintype "passive"))
      (node (ref "R58") (pin "1") (pinfunction "1_1") (pintype "passive"))
    )
    (net (code "88") (name "Net-(LED14-PadA)") (class "Default")
      (node (ref "LED14") (pin "A") (pinfunction "A_A") (pintype "passive"))
      (node (ref "R59") (pin "1") (pinfunction "1_1") (pintype "passive"))
    )
    (net (code "89") (name "Net-(LED15-PadA)") (class "Default")
      (node (ref "LED15") (pin "A") (pinfunction "A_A") (pintype "passive"))
      (node (ref "R60") (pin "1") (pinfunction "1_1") (pintype "passive"))
    )
    (net (code "90") (name "Net-(LED16-PadA)") (class "Default")
      (node (ref "LED16") (pin "A") (pinfunction "A_A") (pintype "passive"))
      (node (ref "R61") (pin "1") (pinfunction "1_1") (pintype "passive"))
    )
    (net (code "91") (name "Net-(LED17-PadA)") (class "Default")
      (node (ref "LED17") (pin "A") (pinfunction "A_A") (pintype "passive"))
      (node (ref "R62") (pin "1") (pinfunction "1_1") (pintype "passive"))
    )
    (net (code "92") (name "Net-(Q1-G)") (class "Default")
      (node (ref "Q1") (pin "4") (pinfunction "G_4") (pintype "passive"))
      (node (ref "R10") (pin "1") (pinfunction "1_1") (pintype "passive"))
    )
    (net (code "93") (name "Net-(Q2-B)") (class "Default")
      (node (ref "Q2") (pin "1") (pinfunction "B_1") (pintype "passive"))
      (node (ref "R19") (pin "2") (pinfunction "2_2") (pintype "passive"))
    )
    (net (code "94") (name "Net-(Q2-C)") (class "Default")
      (node (ref "Q2") (pin "3") (pinfunction "C_3") (pintype "passive"))
      (node (ref "R12") (pin "1") (pinfunction "1_1") (pintype "passive"))
    )
    (net (code "95") (name "Net-(Q3-B)") (class "Default")
      (node (ref "Q3") (pin "1") (pinfunction "B_1") (pintype "passive"))
      (node (ref "R20") (pin "2") (pinfunction "2_2") (pintype "passive"))
    )
    (net (code "96") (name "Net-(Q3-C)") (class "Default")
      (node (ref "Q3") (pin "3") (pinfunction "C_3") (pintype "passive"))
      (node (ref "R14") (pin "1") (pinfunction "1_1") (pintype "passive"))
    )
    (net (code "97") (name "Net-(Q4-G)") (class "Default")
      (node (ref "C37") (pin "2") (pinfunction "2_2") (pintype "passive"))
      (node (ref "D5") (pin "C") (pinfunction "C_C") (pintype "passive"))
      (node (ref "Q4") (pin "4") (pinfunction "G_4") (pintype "passive"))
      (node (ref "Q5") (pin "4") (pinfunction "G_4") (pintype "passive"))
      (node (ref "U11") (pin "3") (pinfunction "GATE_3") (pintype "passive"))
    )
    (net (code "98") (name "Net-(Q6-G)") (class "Default")
      (node (ref "Q6") (pin "4") (pinfunction "G_4") (pintype "passive"))
      (node (ref "R42") (pin "2") (pinfunction "2_2") (pintype "passive"))
    )
    (net (code "99") (name "Net-(Q7-G)") (class "Default")
      (node (ref "Q7") (pin "4") (pinfunction "G_4") (pintype "passive"))
      (node (ref "R41") (pin "2") (pinfunction "2_2") (pintype "passive"))
    )
    (net (code "100") (name "Net-(Q8-G)") (class "Default")
      (node (ref "Q8") (pin "4") (pinfunction "G_4") (pintype "passive"))
      (node (ref "R40") (pin "2") (pinfunction "2_2") (pintype "passive"))
    )
    (net (code "101") (name "Net-(Q9-G)") (class "Default")
      (node (ref "Q9") (pin "4") (pinfunction "G_4") (pintype "passive"))
      (node (ref "R39") (pin "2") (pinfunction "2_2") (pintype "passive"))
    )
    (net (code "102") (name "Net-(R24-Pad1)") (class "Default")
      (node (ref "R24") (pin "1") (pinfunction "1_1") (pintype "passive"))
      (node (ref "R25") (pin "2") (pinfunction "2_2") (pintype "passive"))
    )
    (net (code "103") (name "Net-(U1-OUT)") (class "Default")
      (node (ref "R10") (pin "2") (pinfunction "2_2") (pintype "passive"))
      (node (ref "U1") (pin "5") (pinfunction "OUT_5") (pintype "passive"))
    )
    (net (code "104") (name "Net-(U2-A)") (class "Default")
      (node (ref "R17") (pin "1") (pinfunction "1_1") (pintype "passive"))
      (node (ref "U2") (pin "1") (pinfunction "A_1") (pintype "passive"))
    )
    (net (code "105") (name "Net-(U3-A)") (class "Default")
      (node (ref "R16") (pin "1") (pinfunction "1_1") (pintype "passive"))
      (node (ref "U3") (pin "1") (pinfunction "A_1") (pintype "passive"))
    )
    (net (code "106") (name "Net-(U4-C1+)") (class "Default")
      (node (ref "C8") (pin "1") (pinfunction "1_1") (pintype "passive"))
      (node (ref "U4") (pin "28") (pinfunction "C1+_28") (pintype "passive"))
    )
    (net (code "107") (name "Net-(U4-C1-)") (class "Default")
      (node (ref "C8") (pin "2") (pinfunction "2_2") (pintype "passive"))
      (node (ref "U4") (pin "24") (pinfunction "C1-_24") (pintype "passive"))
    )
    (net (code "108") (name "Net-(U4-C2+)") (class "Default")
      (node (ref "C9") (pin "1") (pinfunction "1_1") (pintype "passive"))
      (node (ref "U4") (pin "1") (pinfunction "C2+_1") (pintype "passive"))
    )
    (net (code "109") (name "Net-(U4-C2-)") (class "Default")
      (node (ref "C9") (pin "2") (pinfunction "2_2") (pintype "passive"))
      (node (ref "U4") (pin "2") (pinfunction "C2-_2") (pintype "passive"))
    )
    (net (code "110") (name "Net-(U4-DIN2)") (class "Default")
      (node (ref "R63") (pin "1") (pinfunction "1_1") (pintype "passive"))
      (node (ref "U4") (pin "13") (pinfunction "DIN2_13") (pintype "passive"))
    )
    (net (code "111") (name "Net-(U4-V+)") (class "Default")
      (node (ref "C13") (pin "1") (pinfunction "1_1") (pintype "passive"))
      (node (ref "U4") (pin "27") (pinfunction "V+_27") (pintype "passive"))
    )
    (net (code "112") (name "Net-(U4-V-)") (class "Default")
      (node (ref "C14") (pin "1") (pinfunction "1_1") (pintype "passive"))
      (node (ref "U4") (pin "3") (pinfunction "V-_3") (pintype "passive"))
    )
    (net (code "113") (name "Net-(U5-VDDA)") (class "Default")
      (node (ref "C10") (pin "2") (pinfunction "2_2") (pintype "passive"))
      (node (ref "C11") (pin "2") (pinfunction "2_2") (pintype "passive"))
      (node (ref "C15") (pin "1") (pinfunction "1_1") (pintype "passive"))
      (node (ref "C16") (pin "1") (pinfunction "1_1") (pintype "passive"))
      (node (ref "R29") (pin "2") (pinfunction "2_2") (pintype "passive"))
      (node (ref "U5") (pin "22") (pinfunction "VREFP_22") (pintype "power_in"))
      (node (ref "U5") (pin "23") (pinfunction "VDDA_23") (pintype "power_in"))
    )
    (net (code "114") (name "Net-(U6-REGOUT)") (class "Default")
      (node (ref "C22") (pin "1") (pinfunction "1_1") (pintype "passive"))
      (node (ref "U6") (pin "11") (pinfunction "REGOUT_11") (pintype "passive"))
    )
    (net (code "115") (name "Net-(U11-OUT)") (class "Default")
      (node (ref "R38") (pin "1") (pinfunction "1_1") (pintype "passive"))
      (node (ref "U11") (pin "1") (pinfunction "OUT_1") (pintype "output"))
    )
    (net (code "116") (name "Net-(U11-SHDN{slash})") (class "Default")
      (node (ref "R33") (pin "2") (pinfunction "2_2") (pintype "passive"))
      (node (ref "U11") (pin "5") (pinfunction "SHDN/_5") (pintype "input"))
    )
    (net (code "117") (name "Net-(U11-SRC)") (class "Default")
      (node (ref "C37") (pin "1") (pinfunction "1_1") (pintype "passive"))
      (node (ref "D5") (pin "A") (pinfunction "A_A") (pintype "passive"))
      (node (ref "Q4") (pin "1") (pinfunction "S_1") (pintype "passive"))
      (node (ref "Q4") (pin "2") (pinfunction "S_2") (pintype "passive"))
      (node (ref "Q4") (pin "3") (pinfunction "S_3") (pintype "passive"))
      (node (ref "Q5") (pin "1") (pinfunction "S_1") (pintype "passive"))
      (node (ref "Q5") (pin "2") (pinfunction "S_2") (pintype "passive"))
      (node (ref "Q5") (pin "3") (pinfunction "S_3") (pintype "passive"))
      (node (ref "U11") (pin "2") (pinfunction "SRC_2") (pintype "input"))
    )
    (net (code "118") (name "Net-(U12-OUT)") (class "Default")
      (node (ref "R39") (pin "1") (pinfunction "1_1") (pintype "passive"))
      (node (ref "U12") (pin "5") (pinfunction "OUT_5") (pintype "passive"))
    )
    (net (code "119") (name "Net-(U13-OUT)") (class "Default")
      (node (ref "R40") (pin "1") (pinfunction "1_1") (pintype "passive"))
      (node (ref "U13") (pin "5") (pinfunction "OUT_5") (pintype "passive"))
    )
    (net (code "120") (name "Net-(U14-OUT)") (class "Default")
      (node (ref "R41") (pin "1") (pinfunction "1_1") (pintype "passive"))
      (node (ref "U14") (pin "5") (pinfunction "OUT_5") (pintype "passive"))
    )
    (net (code "121") (name "Net-(U15-OUT)") (class "Default")
      (node (ref "R42") (pin "1") (pinfunction "1_1") (pintype "passive"))
      (node (ref "U15") (pin "5") (pinfunction "OUT_5") (pintype "passive"))
    )
    (net (code "122") (name "unconnected-(J1-PadLOC1)") (class "Default")
      (node (ref "J1") (pin "LOC1") (pinfunction "LOC1_LOC1") (pintype "bidirectional"))
    )
    (net (code "123") (name "unconnected-(J1-PadLOC2)") (class "Default")
      (node (ref "J1") (pin "LOC2") (pinfunction "LOC2_LOC2") (pintype "bidirectional"))
    )
    (net (code "124") (name "unconnected-(J2-Pad4)") (class "Default")
      (node (ref "J2") (pin "4") (pinfunction "4_4") (pintype "passive"))
    )
    (net (code "125") (name "unconnected-(J4-Pad7)") (class "Default")
      (node (ref "J4") (pin "7") (pinfunction "7_7") (pintype "passive"))
    )
    (net (code "126") (name "unconnected-(J4-Pad8)") (class "Default")
      (node (ref "J4") (pin "8") (pinfunction "8_8") (pintype "passive"))
    )
    (net (code "127") (name "unconnected-(U1-NC-Pad1)") (class "Default")
      (node (ref "U1") (pin "1") (pinfunction "NC_1") (pintype "passive"))
    )
    (net (code "128") (name "unconnected-(U4-*INVALID-Pad21)") (class "Default")
      (node (ref "U4") (pin "21") (pinfunction "*INVALID_21") (pintype "passive"))
    )
    (net (code "129") (name "unconnected-(U4-DOUT2-Pad10)") (class "Default")
      (node (ref "U4") (pin "10") (pinfunction "DOUT2_10") (pintype "passive"))
    )
    (net (code "130") (name "unconnected-(U4-RIN2-Pad5)") (class "Default")
      (node (ref "U4") (pin "5") (pinfunction "RIN2_5") (pintype "passive"))
    )
    (net (code "131") (name "unconnected-(U4-RIN4-Pad7)") (class "Default")
      (node (ref "U4") (pin "7") (pinfunction "RIN4_7") (pintype "passive"))
    )
    (net (code "132") (name "unconnected-(U4-ROUT2-Pad18)") (class "Default")
      (node (ref "U4") (pin "18") (pinfunction "ROUT2_18") (pintype "passive"))
    )
    (net (code "133") (name "unconnected-(U4-ROUT2B-Pad20)") (class "Default")
      (node (ref "U4") (pin "20") (pinfunction "ROUT2B_20") (pintype "passive"))
    )
    (net (code "134") (name "unconnected-(U4-ROUT4-Pad16)") (class "Default")
      (node (ref "U4") (pin "16") (pinfunction "ROUT4_16") (pintype "passive"))
    )
    (net (code "135") (name "unconnected-(U5-PIO0_2-Pad36)") (class "Default")
      (node (ref "U5") (pin "36") (pinfunction "PIO0_2_36") (pintype "bidirectional"))
    )
    (net (code "136") (name "unconnected-(U5-PIO0_3-Pad37)") (class "Default")
      (node (ref "U5") (pin "37") (pinfunction "PIO0_3_37") (pintype "bidirectional"))
    )
    (net (code "137") (name "unconnected-(U5-PIO0_9-Pad44)") (class "Default")
      (node (ref "U5") (pin "44") (pinfunction "PIO0_9_44") (pintype "bidirectional"))
    )
    (net (code "138") (name "unconnected-(U5-PIO0_11-Pad46)") (class "Default")
      (node (ref "U5") (pin "46") (pinfunction "PIO0_11_46") (pintype "bidirectional"))
    )
    (net (code "139") (name "unconnected-(U5-PIO0_12-Pad47)") (class "Default")
      (node (ref "U5") (pin "47") (pinfunction "PIO0_12_47") (pintype "bidirectional"))
    )
    (net (code "140") (name "unconnected-(U5-PIO0_14-Pad49)") (class "Default")
      (node (ref "U5") (pin "49") (pinfunction "PIO0_14_49") (pintype "bidirectional"))
    )
    (net (code "141") (name "unconnected-(U5-PIO0_29-Pad11)") (class "Default")
      (node (ref "U5") (pin "11") (pinfunction "PIO0_29_11") (pintype "bidirectional"))
    )
    (net (code "142") (name "unconnected-(U5-PIO1_11-Pad42)") (class "Default")
      (node (ref "U5") (pin "42") (pinfunction "PIO1_11_42") (pintype "bidirectional"))
    )
    (net (code "143") (name "unconnected-(U5-PIO1_16-Pad7)") (class "Default")
      (node (ref "U5") (pin "7") (pinfunction "PIO1_16_7") (pintype "bidirectional"))
    )
    (net (code "144") (name "unconnected-(U5-RTCXOUT-Pad35)") (class "Default")
      (node (ref "U5") (pin "35") (pinfunction "RTCXOUT_35") (pintype "output"))
    )
    (net (code "145") (name "unconnected-(U6-FSYNC{slash}NC-Pad10)") (class "Default")
      (node (ref "U6") (pin "10") (pinfunction "FSYNC/NC_10") (pintype "no_connect"))
    )
    (net (code "146") (name "unconnected-(U6-INT2-Pad9)") (class "Default")
      (node (ref "U6") (pin "9") (pinfunction "INT2_9") (pintype "output"))
    )
    (net (code "147") (name "unconnected-(U11-FLAG-Pad8)") (class "Default")
      (node (ref "U11") (pin "8") (pinfunction "FLAG_8") (pintype "passive"))
    )
    (net (code "148") (name "unconnected-(U11-IC-Pad7)") (class "Default")
      (node (ref "U11") (pin "7") (pinfunction "IC_7") (pintype "output"))
    )
    (net (code "149") (name "unconnected-(U12-NC-Pad1)") (class "Default")
      (node (ref "U12") (pin "1") (pinfunction "NC_1") (pintype "passive"))
    )
    (net (code "150") (name "unconnected-(U13-NC-Pad1)") (class "Default")
      (node (ref "U13") (pin "1") (pinfunction "NC_1") (pintype "passive"))
    )
    (net (code "151") (name "unconnected-(U14-NC-Pad1)") (class "Default")
      (node (ref "U14") (pin "1") (pinfunction "NC_1") (pintype "passive"))
    )
    (net (code "152") (name "unconnected-(U15-NC-Pad1)") (class "Default")
      (node (ref "U15") (pin "1") (pinfunction "NC_1") (pintype "passive"))
    )
  )
)
